# remo-v0_8_0-rc2-a.net
KiCad netlist of a schematic drawn in EasyEDA Pro
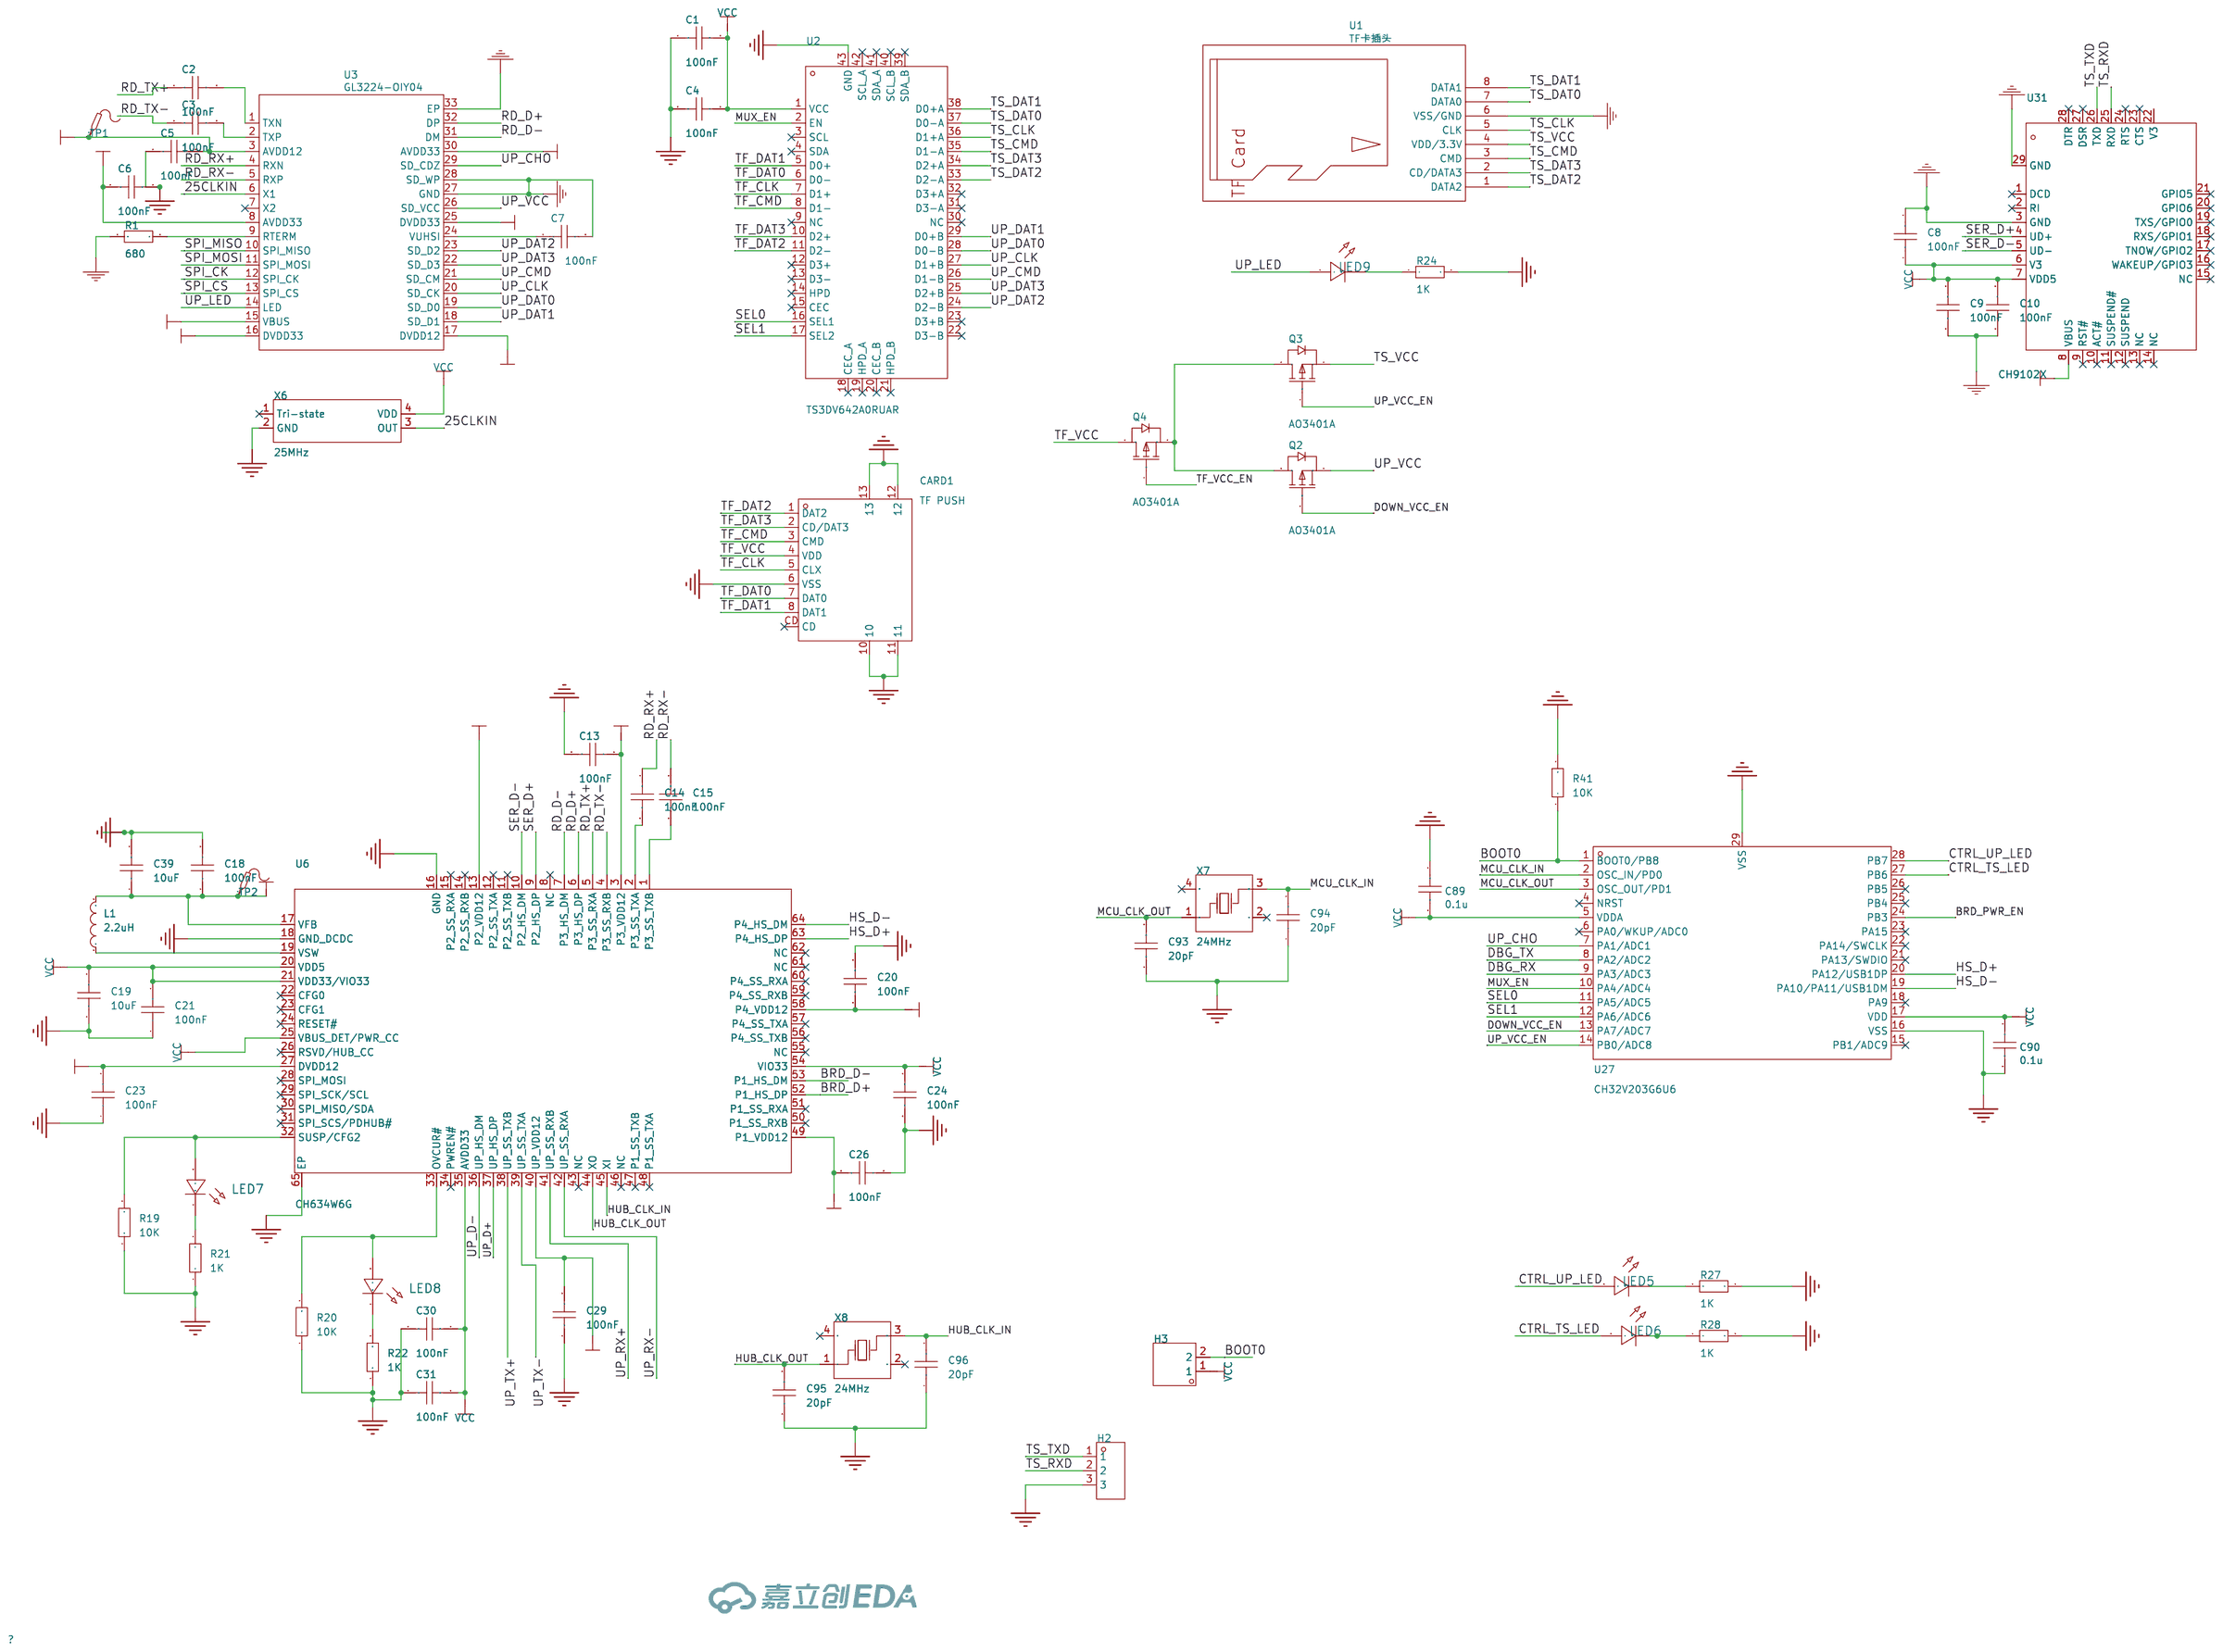
[diagram p0: main]
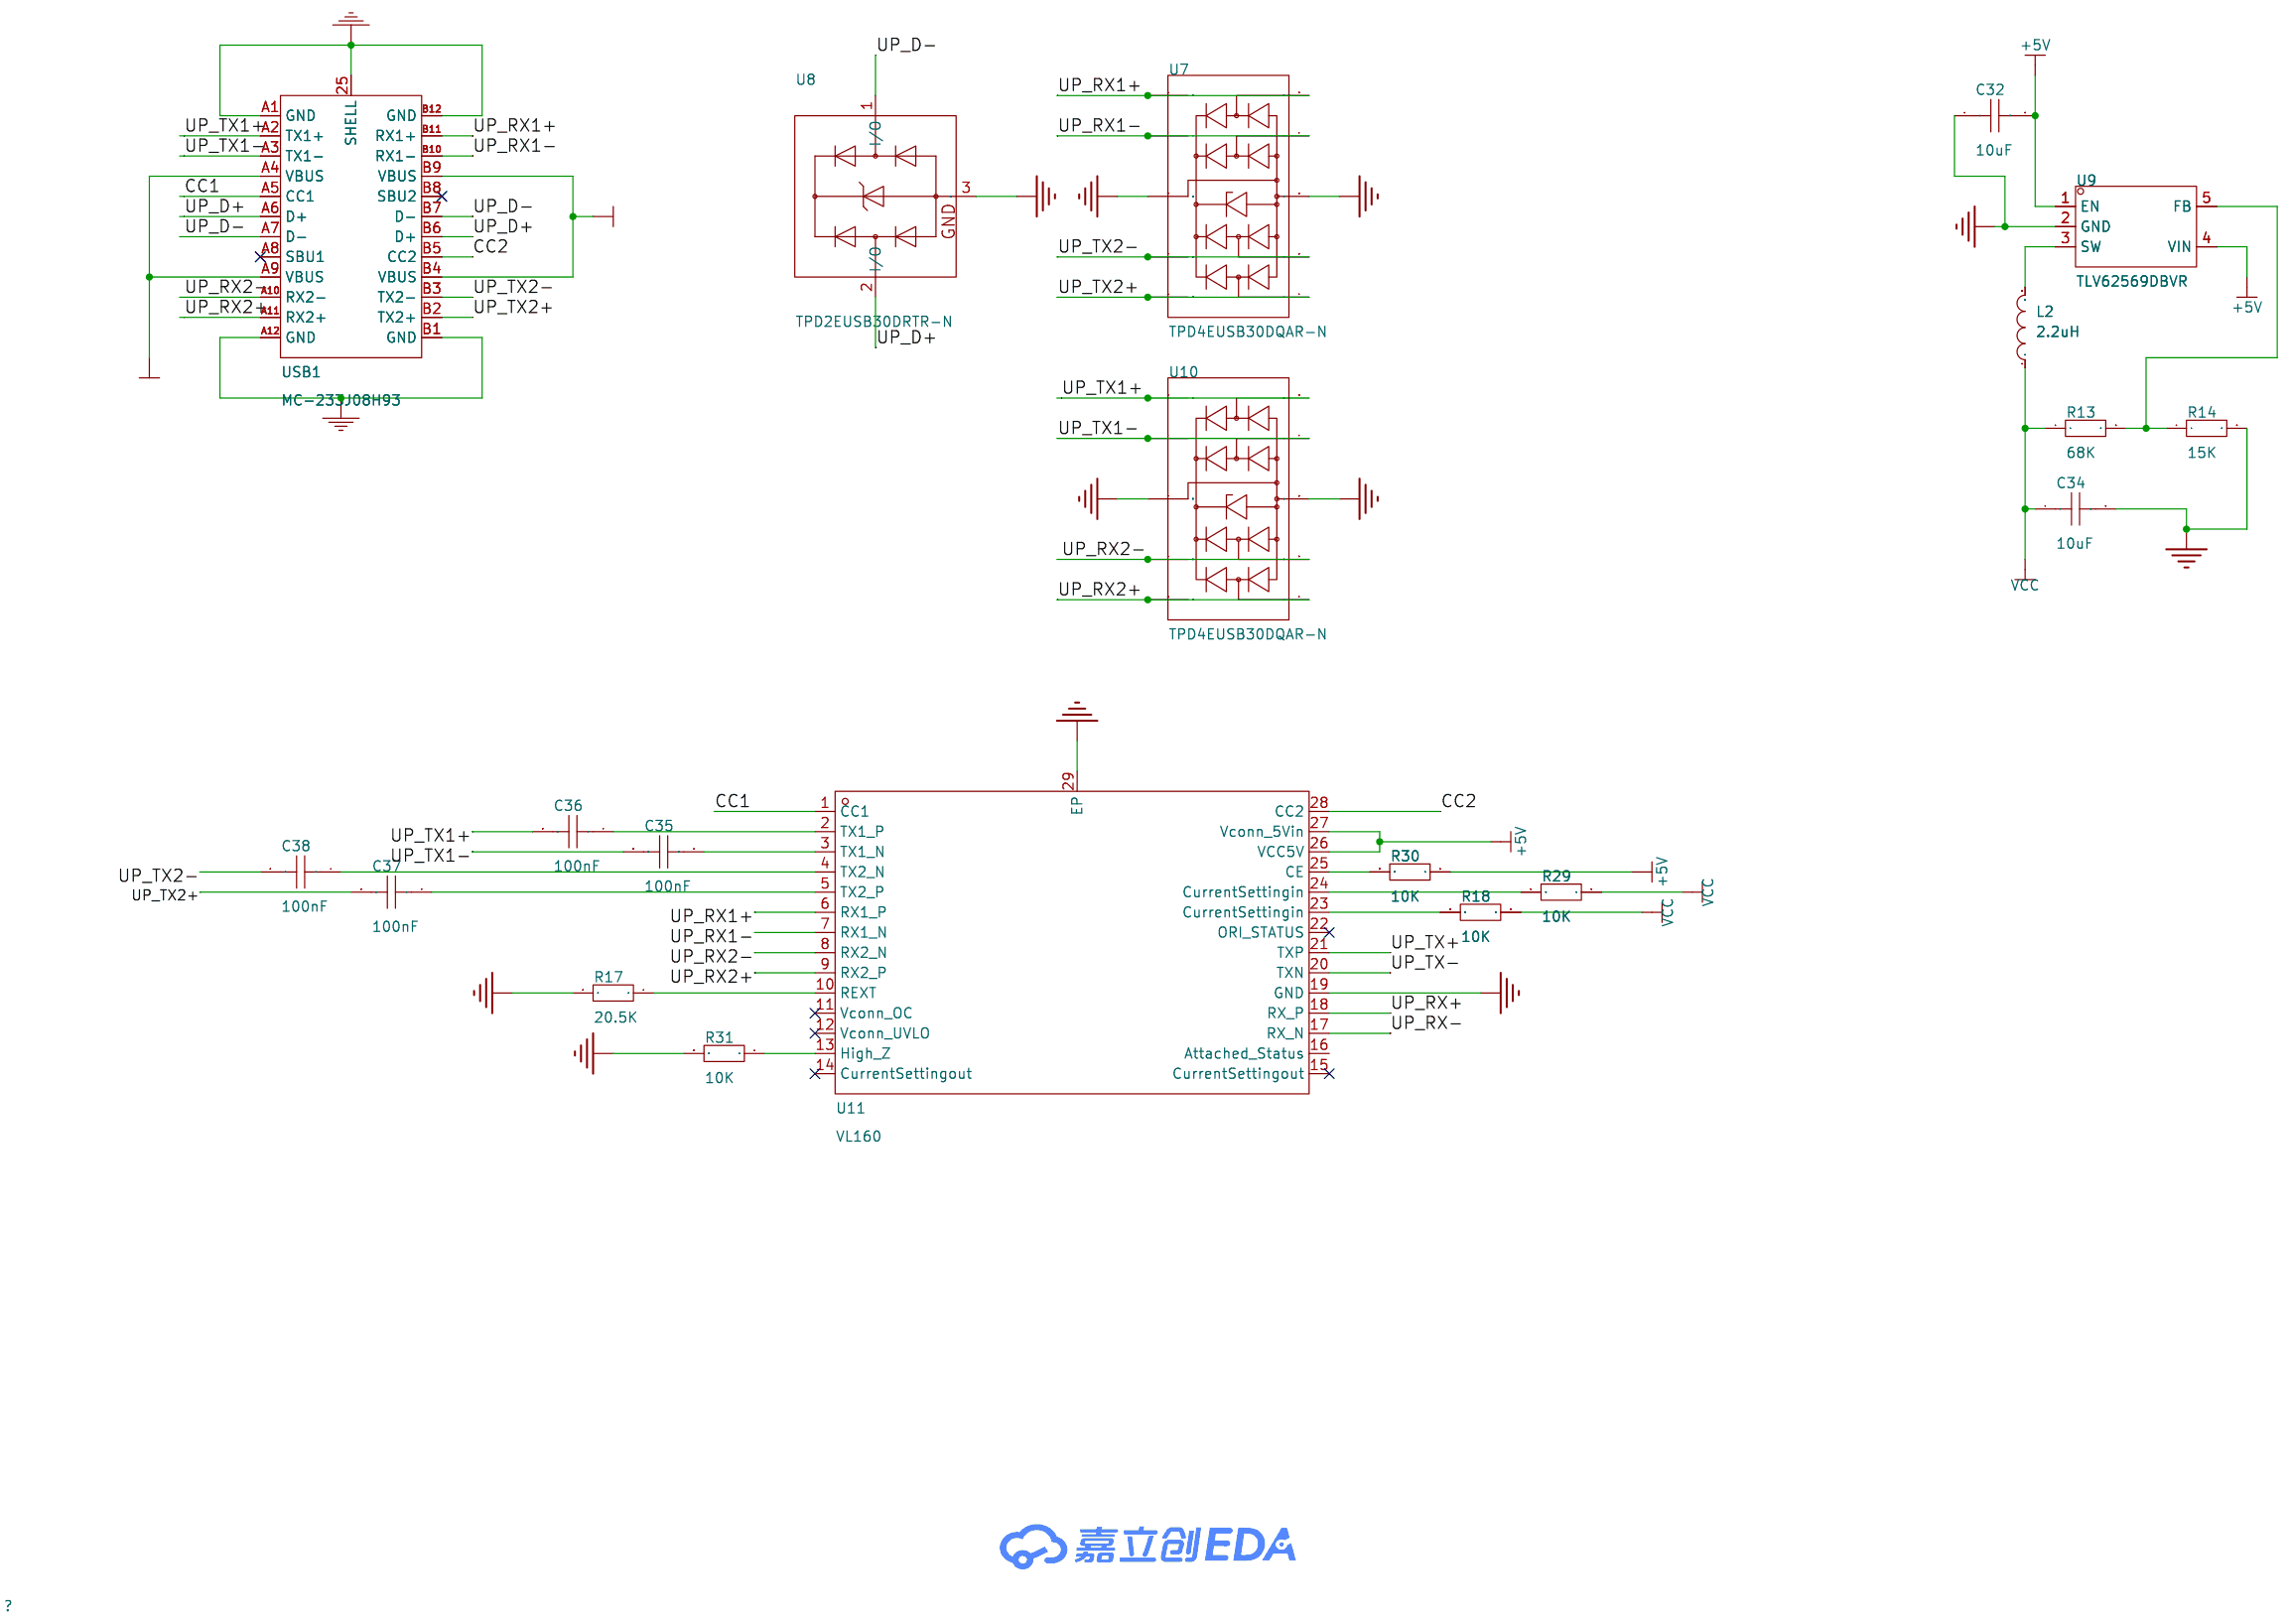
[diagram p1: typec_pwr]
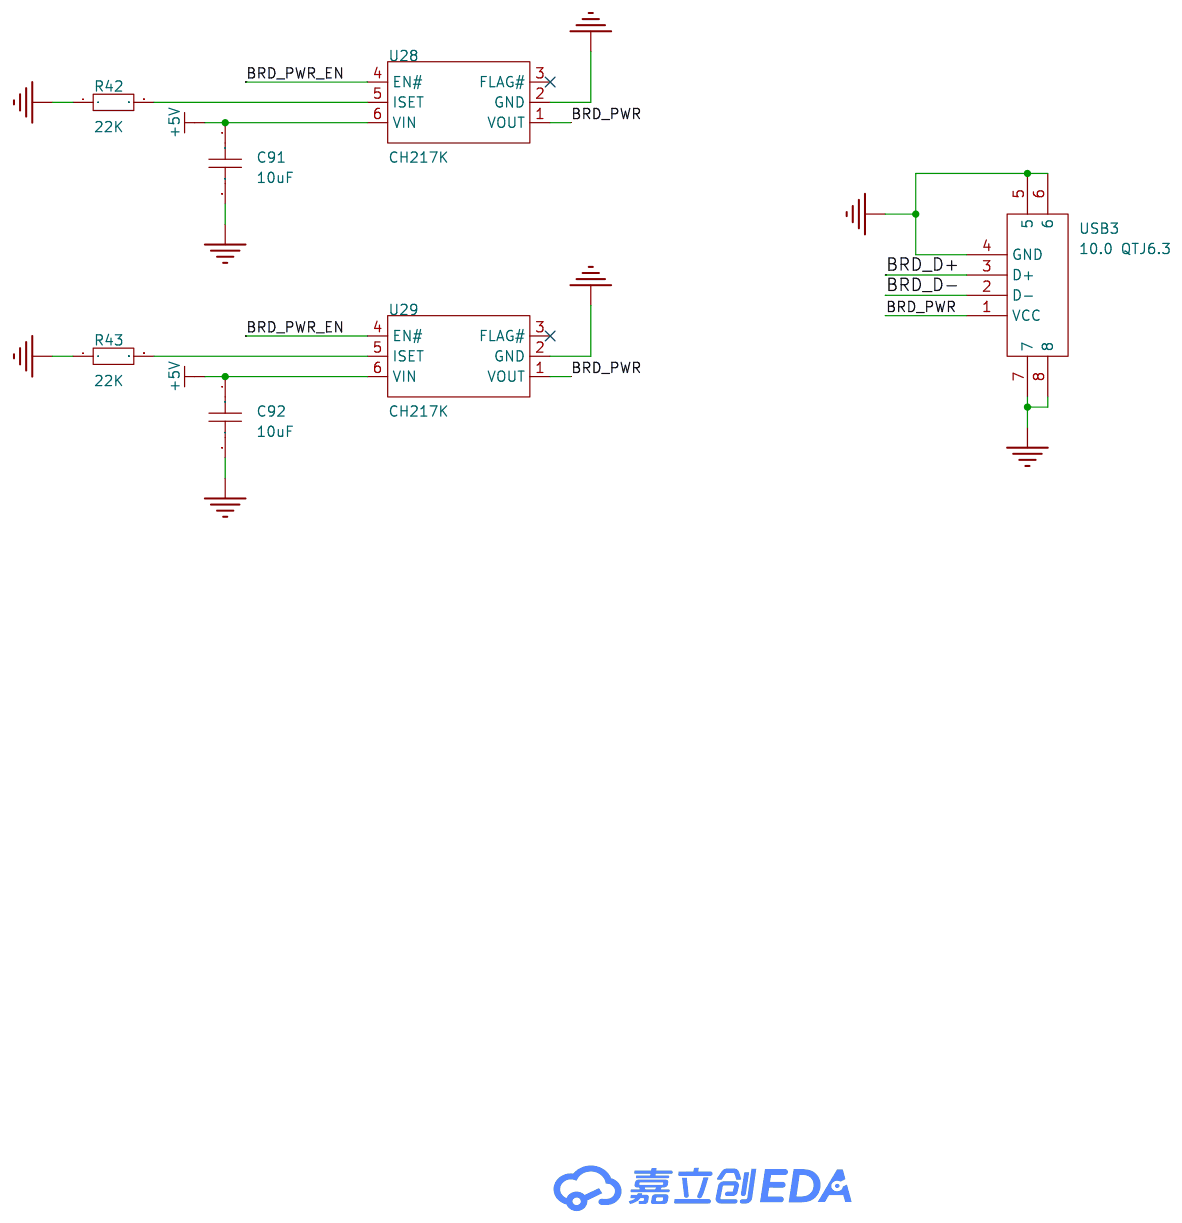
[diagram p2: power_ctrl]

(export (version "E")
  (design (tool "Eeschema 10.0.6"))
  (components
    (comp (ref "C1")
      (value "100nF")
      (footprint "easyedapro:C0402")
      (libsource (lib "easyedapro") (part "CapAcitance"))
    )
    (comp (ref "C2")
      (value "100nF")
      (footprint "easyedapro:C0402")
      (libsource (lib "easyedapro") (part "CapAcitance"))
    )
    (comp (ref "C3")
      (value "100nF")
      (footprint "easyedapro:C0402")
      (libsource (lib "easyedapro") (part "CapAcitance"))
    )
    (comp (ref "C4")
      (value "100nF")
      (footprint "easyedapro:C0402")
      (libsource (lib "easyedapro") (part "CapAcitance"))
    )
    (comp (ref "C5")
      (value "100nF")
      (footprint "easyedapro:C0402")
      (libsource (lib "easyedapro") (part "CapAcitance"))
    )
    (comp (ref "C6")
      (value "100nF")
      (footprint "easyedapro:C0402")
      (libsource (lib "easyedapro") (part "CapAcitance"))
    )
    (comp (ref "C7")
      (value "100nF")
      (footprint "easyedapro:C0402")
      (libsource (lib "easyedapro") (part "CapAcitance"))
    )
    (comp (ref "C8")
      (value "100nF")
      (footprint "easyedapro:C0402")
      (libsource (lib "easyedapro") (part "CapAcitance"))
    )
    (comp (ref "C9")
      (value "100nF")
      (footprint "easyedapro:C0402")
      (libsource (lib "easyedapro") (part "CapAcitance"))
    )
    (comp (ref "C10")
      (value "100nF")
      (footprint "easyedapro:C0402")
      (libsource (lib "easyedapro") (part "CapAcitance"))
    )
    (comp (ref "C13")
      (value "100nF")
      (footprint "easyedapro:C0402")
      (libsource (lib "easyedapro") (part "CapAcitance"))
    )
    (comp (ref "C14")
      (value "100nF")
      (footprint "easyedapro:C0402")
      (libsource (lib "easyedapro") (part "CapAcitance"))
    )
    (comp (ref "C15")
      (value "100nF")
      (footprint "easyedapro:C0402")
      (libsource (lib "easyedapro") (part "CapAcitance"))
    )
    (comp (ref "C18")
      (value "100nF")
      (footprint "easyedapro:C0402")
      (libsource (lib "easyedapro") (part "CapAcitance"))
    )
    (comp (ref "C19")
      (value "10uF")
      (footprint "easyedapro:C0402")
      (libsource (lib "easyedapro") (part "CapAcitance"))
    )
    (comp (ref "C20")
      (value "100nF")
      (footprint "easyedapro:C0402")
      (libsource (lib "easyedapro") (part "CapAcitance"))
    )
    (comp (ref "C21")
      (value "100nF")
      (footprint "easyedapro:C0402")
      (libsource (lib "easyedapro") (part "CapAcitance"))
    )
    (comp (ref "C23")
      (value "100nF")
      (footprint "easyedapro:C0402")
      (libsource (lib "easyedapro") (part "CapAcitance"))
    )
    (comp (ref "C24")
      (value "100nF")
      (footprint "easyedapro:C0402")
      (libsource (lib "easyedapro") (part "CapAcitance"))
    )
    (comp (ref "C26")
      (value "100nF")
      (footprint "easyedapro:C0402")
      (libsource (lib "easyedapro") (part "CapAcitance"))
    )
    (comp (ref "C29")
      (value "100nF")
      (footprint "easyedapro:C0402")
      (libsource (lib "easyedapro") (part "CapAcitance"))
    )
    (comp (ref "C30")
      (value "100nF")
      (footprint "easyedapro:C0402")
      (libsource (lib "easyedapro") (part "CapAcitance"))
    )
    (comp (ref "C31")
      (value "100nF")
      (footprint "easyedapro:C0402")
      (libsource (lib "easyedapro") (part "CapAcitance"))
    )
    (comp (ref "C39")
      (value "10uF")
      (footprint "easyedapro:C0402")
      (libsource (lib "easyedapro") (part "CapAcitance"))
    )
    (comp (ref "C89")
      (value "0.1u")
      (footprint "easyedapro:C0603")
      (libsource (lib "easyedapro") (part "0.1u"))
    )
    (comp (ref "C90")
      (value "0.1u")
      (footprint "easyedapro:C0603")
      (libsource (lib "easyedapro") (part "0.1u"))
    )
    (comp (ref "C93")
      (value "20pF")
      (footprint "easyedapro:C0402")
      (libsource (lib "easyedapro") (part "CapAcitance"))
    )
    (comp (ref "C94")
      (value "20pF")
      (footprint "easyedapro:C0402")
      (libsource (lib "easyedapro") (part "CapAcitance"))
    )
    (comp (ref "C95")
      (value "20pF")
      (footprint "easyedapro:C0402")
      (libsource (lib "easyedapro") (part "CapAcitance"))
    )
    (comp (ref "C96")
      (value "20pF")
      (footprint "easyedapro:C0402")
      (libsource (lib "easyedapro") (part "CapAcitance"))
    )
    (comp (ref "CARD1")
      (value "TF PUSH")
      (footprint "easyedapro:TF-SMD_TF-PUSH")
      (description "卡连接方式:自弹式;卡类型:MicroSD卡(TF卡);连接器类型:卡座;本体最大高度:2mm;工作温度范围:-20°C~+90°C;")
      (fields (field (name "Manufacturer") "SHOU HAN(首韩)"))
      (libsource (lib "easyedapro") (part "TF PUSH"))
    )
    (comp (ref "H2")
      (value "~")
      (footprint "easyedapro:HDR-TH_3P-P2.54-V-M")
      (libsource (lib "easyedapro") (part "PZ254V-11-03P_C2937625"))
    )
    (comp (ref "H3")
      (value "~")
      (footprint "easyedapro:HDR-TH_2P-P2.54-V-M-1")
      (libsource (lib "easyedapro") (part "210S-1*2P L=11.6MMGold-plated black"))
    )
    (comp (ref "L1")
      (value "2.2uH")
      (footprint "easyedapro:IND-SMD_L2.5-W2.0_MHCHL2520")
      (description "电感值:2.2uH;精度:±20%;额定电流:3A;饱和电流(Isat):3.8A;类型:一体成型电感;")
      (fields
        (field (name "Manufacturer Part") "FTC252012S2R2MBCA")
        (field (name "Manufacturer") "cjiang(长江微电)")
      )
      (libsource (lib "easyedapro") (part "FTC252012S2R2MBCA"))
    )
    (comp (ref "LED5")
      (value "~")
      (footprint "easyedapro:LED_0603")
      (libsource (lib "easyedapro") (part "LED_R"))
    )
    (comp (ref "LED6")
      (value "~")
      (footprint "easyedapro:LED_0603")
      (libsource (lib "easyedapro") (part "LED_R"))
    )
    (comp (ref "LED7")
      (value "~")
      (footprint "easyedapro:LED_0603")
      (libsource (lib "easyedapro") (part "LED_R"))
    )
    (comp (ref "LED8")
      (value "~")
      (footprint "easyedapro:LED_0603")
      (libsource (lib "easyedapro") (part "LED_R"))
    )
    (comp (ref "LED9")
      (value "~")
      (footprint "easyedapro:LED_0603")
      (libsource (lib "easyedapro") (part "LED_R"))
    )
    (comp (ref "Q2")
      (value "AO3401A")
      (footprint "easyedapro:SOT-23_L2.9-W1.3-P1.90-LS2.4-BR")
      (fields (field (name "Manufacturer") "AOS"))
      (libsource (lib "easyedapro") (part "AO3401A"))
    )
    (comp (ref "Q3")
      (value "AO3401A")
      (footprint "easyedapro:SOT-23_L2.9-W1.3-P1.90-LS2.4-BR")
      (fields (field (name "Manufacturer") "AOS"))
      (libsource (lib "easyedapro") (part "AO3401A"))
    )
    (comp (ref "Q4")
      (value "AO3401A")
      (footprint "easyedapro:SOT-23_L2.9-W1.3-P1.90-LS2.4-BR")
      (fields (field (name "Manufacturer") "AOS"))
      (libsource (lib "easyedapro") (part "AO3401A"))
    )
    (comp (ref "R1") (value "680") (footprint "easyedapro:R0603") (libsource (lib "easyedapro") (part "电阻")))
    (comp (ref "R19") (value "10K") (footprint "easyedapro:R0603") (libsource (lib "easyedapro") (part "电阻")))
    (comp (ref "R20") (value "10K") (footprint "easyedapro:R0603") (libsource (lib "easyedapro") (part "电阻")))
    (comp (ref "R21") (value "1K") (footprint "easyedapro:R0603") (libsource (lib "easyedapro") (part "电阻")))
    (comp (ref "R22") (value "1K") (footprint "easyedapro:R0603") (libsource (lib "easyedapro") (part "电阻")))
    (comp (ref "R24") (value "1K") (footprint "easyedapro:R0603") (libsource (lib "easyedapro") (part "电阻")))
    (comp (ref "R27") (value "1K") (footprint "easyedapro:R0603") (libsource (lib "easyedapro") (part "电阻")))
    (comp (ref "R28") (value "1K") (footprint "easyedapro:R0603") (libsource (lib "easyedapro") (part "电阻")))
    (comp (ref "R41") (value "10K") (footprint "easyedapro:R0603") (libsource (lib "easyedapro") (part "电阻")))
    (comp (ref "TP1")
      (value "~")
      (footprint "easyedapro:Test-Point-0.5mm")
      (description "Test Point 测试点")
      (libsource (lib "easyedapro") (part "Test-Point"))
    )
    (comp (ref "TP2")
      (value "~")
      (footprint "easyedapro:Test-Point-0.5mm")
      (description "Test Point 测试点")
      (libsource (lib "easyedapro") (part "Test-Point"))
    )
    (comp (ref "U1")
      (value "TF卡插头")
      (footprint "easyedapro:TF卡封装")
      (libsource (lib "easyedapro") (part "TF卡插头"))
    )
    (comp (ref "U2")
      (value "TS3DV642A0RUAR")
      (footprint "easyedapro:WFQFN-42_L9.0-W3.5-P0.50-BL-EP")
      (description "开关电路:单刀双掷(SPDT);通道数:12;导通电阻(Ron@VCC):9.5Ω;")
      (fields (field (name "Manufacturer") "TI(德州仪器)"))
      (libsource (lib "easyedapro") (part "TS3DV642A0RUAR"))
    )
    (comp (ref "U3")
      (value "GL3224-OIY04")
      (footprint "easyedapro:HQFN-32_L5.0-W5.0-P0.50-BL-EP3.0")
      (fields (field (name "Manufacturer") "GENESYS(创惟)"))
      (libsource (lib "easyedapro") (part "GL3224-OIY04"))
    )
    (comp (ref "U6")
      (value "CH634W6G")
      (footprint "easyedapro:QFN-64_L8.0-W8.0-P0.40-TL-EP6.2")
      (fields (field (name "Manufacturer") "WCH(南京沁恒)"))
      (libsource (lib "easyedapro") (part "CH634W6G"))
    )
    (comp (ref "U27")
      (value "CH32V203G6U6")
      (footprint "easyedapro:QFN-28_L4.0-W4.0-P0.40-BL-EP2.7")
      (description "CPU内核:RISC-V;GPIO端口数量:-;工作电压范围:-;CPU最大主频:-;程序存储器类型:-;应用领域:-;")
      (fields (field (name "Manufacturer") "WCH(南京沁恒)"))
      (libsource (lib "easyedapro") (part "CH32V203G6U6"))
    )
    (comp (ref "U31")
      (value "CH9102X")
      (footprint "easyedapro:TQFN-28_L5.0-W5.0-P0.50-BL-EP2.7")
      (description "应用功能:USB转UART;接口协议:USB 2.0;通道数:-;数据速率:4Mbps;")
      (fields (field (name "Manufacturer") "WCH(南京沁恒)"))
      (libsource (lib "easyedapro") (part "CH9102X_C5187522"))
    )
    (comp (ref "X6")
      (value "25MHz")
      (footprint "easyedapro:OSC-SMD_4P-L2.5-W2.0-BL-1")
      (description "频率:25MHz;常温频差:±10ppm;输出模式:CMOS;工作电压:1.8V~3.3V;频率稳定度:±20ppm;")
      (fields (field (name "Manufacturer Part") "OT252025MJBA4SL") (field (name "Manufacturer") "YXC(扬兴晶振)"))
      (libsource (lib "easyedapro") (part "OT252025MJBA4SL"))
    )
    (comp (ref "X7")
      (value "24MHz")
      (footprint "easyedapro:CRYSTAL-SMD_4P-L3.2-W2.5-BL")
      (description "晶振类型:贴片无源晶振;频率:24MHz;频率公差:±10ppm;频率稳定度:±30ppm;负载电容:20pF;工作温度:-40°C~+85°C;")
      (fields (field (name "Manufacturer Part") "X322524MSB4SI") (field (name "Manufacturer") "YXC(扬兴科技)"))
      (libsource (lib "easyedapro") (part "X322524MSB4SI"))
    )
    (comp (ref "X8")
      (value "24MHz")
      (footprint "easyedapro:CRYSTAL-SMD_4P-L3.2-W2.5-BL")
      (description "晶振类型:贴片无源晶振;频率:24MHz;频率公差:±10ppm;频率稳定度:±30ppm;负载电容:20pF;工作温度:-40°C~+85°C;")
      (fields (field (name "Manufacturer Part") "X322524MSB4SI") (field (name "Manufacturer") "YXC(扬兴科技)"))
      (libsource (lib "easyedapro") (part "X322524MSB4SI"))
    )
    (comp (ref "C32")
      (value "10uF")
      (footprint "easyedapro:C0402")
      (libsource (lib "easyedapro") (part "CapAcitance"))
    )
    (comp (ref "C34")
      (value "10uF")
      (footprint "easyedapro:C0402")
      (libsource (lib "easyedapro") (part "CapAcitance"))
    )
    (comp (ref "C35")
      (value "100nF")
      (footprint "easyedapro:C0402")
      (libsource (lib "easyedapro") (part "CapAcitance"))
    )
    (comp (ref "C36")
      (value "100nF")
      (footprint "easyedapro:C0402")
      (libsource (lib "easyedapro") (part "CapAcitance"))
    )
    (comp (ref "C37")
      (value "100nF")
      (footprint "easyedapro:C0402")
      (libsource (lib "easyedapro") (part "CapAcitance"))
    )
    (comp (ref "C38")
      (value "100nF")
      (footprint "easyedapro:C0402")
      (libsource (lib "easyedapro") (part "CapAcitance"))
    )
    (comp (ref "L2")
      (value "2.2uH")
      (footprint "easyedapro:IND-SMD_L2.5-W2.0_MHCHL2520")
      (description "电感值:2.2uH;精度:±20%;额定电流:3A;饱和电流(Isat):3.8A;类型:一体成型电感;")
      (fields
        (field (name "Manufacturer Part") "FTC252012S2R2MBCA")
        (field (name "Manufacturer") "cjiang(长江微电)")
      )
      (libsource (lib "easyedapro") (part "FTC252012S2R2MBCA"))
    )
    (comp (ref "R13") (value "68K") (footprint "easyedapro:R0603") (libsource (lib "easyedapro") (part "电阻")))
    (comp (ref "R14") (value "15K") (footprint "easyedapro:R0603") (libsource (lib "easyedapro") (part "电阻")))
    (comp (ref "R17")
      (value "20.5K")
      (footprint "easyedapro:R0603")
      (libsource (lib "easyedapro") (part "电阻"))
    )
    (comp (ref "R18") (value "10K") (footprint "easyedapro:R0603") (libsource (lib "easyedapro") (part "电阻")))
    (comp (ref "R29") (value "10K") (footprint "easyedapro:R0603") (libsource (lib "easyedapro") (part "电阻")))
    (comp (ref "R30") (value "10K") (footprint "easyedapro:R0603") (libsource (lib "easyedapro") (part "电阻")))
    (comp (ref "R31") (value "10K") (footprint "easyedapro:R0603") (libsource (lib "easyedapro") (part "电阻")))
    (comp (ref "U7")
      (value "TPD4EUSB30DQAR-N")
      (footprint "easyedapro:DFN-10_L2.5-W1.0-P0.50-BL-A")
      (description "极性:单向;反向截止电压(Vrwm):5V;")
      (fields (field (name "Manufacturer") "BORN(伯恩半导体)"))
      (libsource (lib "easyedapro") (part "TPD4EUSB30DQAR-N"))
    )
    (comp (ref "U8")
      (value "TPD2EUSB30DRTR-N")
      (footprint "easyedapro:SOT-723_L1.2-W0.8-P0.40-LS1.2-BR")
      (description "极性:单向;反向截止电压(Vrwm):5V;")
      (fields (field (name "Manufacturer") "BORN(伯恩半导体)"))
      (libsource (lib "easyedapro") (part "TPD2EUSB30DRTR-N"))
    )
    (comp (ref "U9")
      (value "TLV62569DBVR")
      (footprint "easyedapro:SOT-23-5_L3.0-W1.7-P0.95-LS2.8-BR")
      (description "功能类型:降压型;输出类型:可调;工作电压:2.5V~5.5V;输出电压:600mV~5.5V;输出电流:2A;")
      (fields (field (name "Manufacturer") "TI(德州仪器)"))
      (libsource (lib "easyedapro") (part "TLV62569DBVR"))
    )
    (comp (ref "U10")
      (value "TPD4EUSB30DQAR-N")
      (footprint "easyedapro:DFN-10_L2.5-W1.0-P0.50-BL-A")
      (description "极性:单向;反向截止电压(Vrwm):5V;")
      (fields (field (name "Manufacturer") "BORN(伯恩半导体)"))
      (libsource (lib "easyedapro") (part "TPD4EUSB30DQAR-N"))
    )
    (comp (ref "U11")
      (value "VL160")
      (footprint "easyedapro:MQFN-28_L4.5-W3.5-P0.40-BL-EP")
      (description "应用功能:-;接口协议:-;")
      (libsource (lib "easyedapro") (part "VL160"))
    )
    (comp (ref "USB1")
      (value "MC-233J08H93")
      (footprint "easyedapro:USB-C-SMD_TYPE-C-31-M-20")
      (fields (field (name "Manufacturer") "HANBO(汉博)"))
      (libsource (lib "easyedapro") (part "MC-233J08H93"))
    )
    (comp (ref "C91")
      (value "10uF")
      (footprint "easyedapro:C0402")
      (libsource (lib "easyedapro") (part "CapAcitance"))
    )
    (comp (ref "C92")
      (value "10uF")
      (footprint "easyedapro:C0402")
      (libsource (lib "easyedapro") (part "CapAcitance"))
    )
    (comp (ref "R42") (value "22K") (footprint "easyedapro:R0603") (libsource (lib "easyedapro") (part "电阻")))
    (comp (ref "R43") (value "22K") (footprint "easyedapro:R0603") (libsource (lib "easyedapro") (part "电阻")))
    (comp (ref "U28")
      (value "CH217K")
      (footprint "easyedapro:SOT-23-6_L2.9-W1.6-P0.95-LS2.8-BL")
      (description "类型:负载开关;通道数:1;输入控制逻辑:低电平有效;输出电流:2.7A;工作电压:2.7V~5.5V;导通电阻:70mΩ;")
      (fields (field (name "Manufacturer") "WCH(南京沁恒)"))
      (libsource (lib "easyedapro") (part "CH217K"))
    )
    (comp (ref "U29")
      (value "CH217K")
      (footprint "easyedapro:SOT-23-6_L2.9-W1.6-P0.95-LS2.8-BL")
      (description "类型:负载开关;通道数:1;输入控制逻辑:低电平有效;输出电流:2.7A;工作电压:2.7V~5.5V;导通电阻:70mΩ;")
      (fields (field (name "Manufacturer") "WCH(南京沁恒)"))
      (libsource (lib "easyedapro") (part "CH217K"))
    )
    (comp (ref "USB3")
      (value "10.0 QTJ6.3")
      (footprint "easyedapro:USB-A-SMD_10.0-QTJ6.3")
      (description "连接器类型:Type-A;标准:USB 2.0;公母:母;安装方式:卧贴;触点数量:4P;端口数量:1;额定电流 - 电源:1.5A;工作温度范围:-25°C~+85°C;")
      (fields (field (name "Manufacturer") "SHOU HAN(首韩)"))
      (libsource (lib "easyedapro") (part "10.0 QTJ6.3"))
    )
  )
  (nets
    (net (code "1") (name "+5V") (class "Default")
      (node (ref "C32") (pin "2") (pinfunction "2_2") (pintype "input"))
      (node (ref "C91") (pin "1") (pinfunction "1_1") (pintype "input"))
      (node (ref "C92") (pin "1") (pinfunction "1_1") (pintype "input"))
      (node (ref "R30") (pin "1") (pinfunction "1_1") (pintype "input"))
      (node (ref "U11") (pin "26") (pinfunction "VCC5V_26") (pintype "unspecified"))
      (node (ref "U11") (pin "27") (pinfunction "Vconn_5Vin_27") (pintype "unspecified"))
      (node (ref "U28") (pin "6") (pinfunction "VIN_6") (pintype "unspecified"))
      (node (ref "U29") (pin "6") (pinfunction "VIN_6") (pintype "unspecified"))
      (node (ref "U31") (pin "8") (pinfunction "VBUS_8") (pintype "unspecified"))
      (node (ref "U9") (pin "1") (pinfunction "EN_1") (pintype "unspecified"))
      (node (ref "U9") (pin "4") (pinfunction "VIN_4") (pintype "unspecified"))
      (node (ref "USB1") (pin "A4") (pinfunction "VBUS_A4") (pintype "unspecified"))
      (node (ref "USB1") (pin "A9") (pinfunction "VBUS_A9") (pintype "unspecified"))
      (node (ref "USB1") (pin "B4") (pinfunction "VBUS_B4") (pintype "unspecified"))
      (node (ref "USB1") (pin "B9") (pinfunction "VBUS_B9") (pintype "unspecified"))
    )
    (net (code "2") (name "25CLKIN") (class "Default")
      (node (ref "U3") (pin "6") (pinfunction "X1_6") (pintype "unspecified"))
      (node (ref "X6") (pin "3") (pinfunction "OUT_3") (pintype "unspecified"))
    )
    (net (code "3") (name "BOOT0") (class "Default")
      (node (ref "H3") (pin "2") (pinfunction "2_2") (pintype "unspecified"))
      (node (ref "R41") (pin "1") (pinfunction "1_1") (pintype "input"))
      (node (ref "U27") (pin "1") (pinfunction "BOOT0/PB8_1") (pintype "unspecified"))
    )
    (net (code "4") (name "BRD_D+") (class "Default")
      (node (ref "U6") (pin "52") (pinfunction "P1_HS_DP_52") (pintype "unspecified"))
      (node (ref "USB3") (pin "3") (pinfunction "D+_3") (pintype "unspecified"))
    )
    (net (code "5") (name "BRD_D-") (class "Default")
      (node (ref "U6") (pin "53") (pinfunction "P1_HS_DM_53") (pintype "unspecified"))
      (node (ref "USB3") (pin "2") (pinfunction "D-_2") (pintype "unspecified"))
    )
    (net (code "6") (name "BRD_PWR") (class "Default")
      (node (ref "U28") (pin "1") (pinfunction "VOUT_1") (pintype "unspecified"))
      (node (ref "U29") (pin "1") (pinfunction "VOUT_1") (pintype "unspecified"))
      (node (ref "USB3") (pin "1") (pinfunction "VCC_1") (pintype "unspecified"))
    )
    (net (code "7") (name "BRD_PWR_EN") (class "Default")
      (node (ref "U27") (pin "24") (pinfunction "PB3_24") (pintype "unspecified"))
      (node (ref "U28") (pin "4") (pinfunction "EN#_4") (pintype "unspecified"))
      (node (ref "U29") (pin "4") (pinfunction "EN#_4") (pintype "unspecified"))
    )
    (net (code "8") (name "CC1") (class "Default")
      (node (ref "U11") (pin "1") (pinfunction "CC1_1") (pintype "unspecified"))
      (node (ref "USB1") (pin "A5") (pinfunction "CC1_A5") (pintype "unspecified"))
    )
    (net (code "9") (name "CC2") (class "Default")
      (node (ref "U11") (pin "28") (pinfunction "CC2_28") (pintype "unspecified"))
      (node (ref "USB1") (pin "B5") (pinfunction "CC2_B5") (pintype "unspecified"))
    )
    (net (code "10") (name "CTRL_TS_LED") (class "Default")
      (node (ref "LED6") (pin "2") (pinfunction "A_2") (pintype "input"))
      (node (ref "U27") (pin "27") (pinfunction "PB6_27") (pintype "unspecified"))
    )
    (net (code "11") (name "CTRL_UP_LED") (class "Default")
      (node (ref "LED5") (pin "2") (pinfunction "A_2") (pintype "input"))
      (node (ref "U27") (pin "28") (pinfunction "PB7_28") (pintype "unspecified"))
    )
    (net (code "12") (name "DBG_RX") (class "Default")
      (node (ref "U27") (pin "9") (pinfunction "PA3/ADC3_9") (pintype "unspecified"))
    )
    (net (code "13") (name "DBG_TX") (class "Default")
      (node (ref "U27") (pin "8") (pinfunction "PA2/ADC2_8") (pintype "unspecified"))
    )
    (net (code "14") (name "DOWN_VCC_EN") (class "Default")
      (node (ref "Q2") (pin "1") (pinfunction "G_1") (pintype "unspecified"))
      (node (ref "U27") (pin "13") (pinfunction "PA7/ADC7_13") (pintype "unspecified"))
    )
    (net (code "15") (name "GND") (class "Default")
      (node (ref "C1") (pin "1") (pinfunction "1_1") (pintype "input"))
      (node (ref "C10") (pin "1") (pinfunction "1_1") (pintype "input"))
      (node (ref "C13") (pin "2") (pinfunction "2_2") (pintype "input"))
      (node (ref "C18") (pin "2") (pinfunction "2_2") (pintype "input"))
      (node (ref "C19") (pin "1") (pinfunction "1_1") (pintype "input"))
      (node (ref "C20") (pin "2") (pinfunction "2_2") (pintype "input"))
      (node (ref "C21") (pin "1") (pinfunction "1_1") (pintype "input"))
      (node (ref "C23") (pin "1") (pinfunction "1_1") (pintype "input"))
      (node (ref "C24") (pin "2") (pinfunction "2_2") (pintype "input"))
      (node (ref "C26") (pin "1") (pinfunction "1_1") (pintype "input"))
      (node (ref "C29") (pin "1") (pinfunction "1_1") (pintype "input"))
      (node (ref "C30") (pin "1") (pinfunction "1_1") (pintype "input"))
      (node (ref "C31") (pin "1") (pinfunction "1_1") (pintype "input"))
      (node (ref "C32") (pin "1") (pinfunction "1_1") (pintype "input"))
      (node (ref "C34") (pin "2") (pinfunction "2_2") (pintype "input"))
      (node (ref "C39") (pin "2") (pinfunction "2_2") (pintype "input"))
      (node (ref "C4") (pin "1") (pinfunction "1_1") (pintype "input"))
      (node (ref "C5") (pin "1") (pinfunction "1_1") (pintype "input"))
      (node (ref "C6") (pin "2") (pinfunction "2_2") (pintype "input"))
      (node (ref "C7") (pin "2") (pinfunction "2_2") (pintype "input"))
      (node (ref "C8") (pin "2") (pinfunction "2_2") (pintype "input"))
      (node (ref "C89") (pin "1") (pinfunction "1_1") (pintype "unspecified"))
      (node (ref "C9") (pin "1") (pinfunction "1_1") (pintype "input"))
      (node (ref "C90") (pin "2") (pinfunction "2_2") (pintype "unspecified"))
      (node (ref "C91") (pin "2") (pinfunction "2_2") (pintype "input"))
      (node (ref "C92") (pin "2") (pinfunction "2_2") (pintype "input"))
      (node (ref "C93") (pin "1") (pinfunction "1_1") (pintype "input"))
      (node (ref "C94") (pin "1") (pinfunction "1_1") (pintype "input"))
      (node (ref "C95") (pin "1") (pinfunction "1_1") (pintype "input"))
      (node (ref "C96") (pin "1") (pinfunction "1_1") (pintype "input"))
      (node (ref "CARD1") (pin "10") (pinfunction "10_10") (pintype "unspecified"))
      (node (ref "CARD1") (pin "11") (pinfunction "11_11") (pintype "unspecified"))
      (node (ref "CARD1") (pin "12") (pinfunction "12_12") (pintype "unspecified"))
      (node (ref "CARD1") (pin "13") (pinfunction "13_13") (pintype "unspecified"))
      (node (ref "CARD1") (pin "6") (pinfunction "VSS_6") (pintype "unspecified"))
      (node (ref "H2") (pin "3") (pinfunction "3_3") (pintype "input"))
      (node (ref "R1") (pin "1") (pinfunction "1_1") (pintype "input"))
      (node (ref "R14") (pin "2") (pinfunction "2_2") (pintype "input"))
      (node (ref "R17") (pin "2") (pinfunction "2_2") (pintype "input"))
      (node (ref "R19") (pin "1") (pinfunction "1_1") (pintype "input"))
      (node (ref "R20") (pin "1") (pinfunction "1_1") (pintype "input"))
      (node (ref "R21") (pin "1") (pinfunction "1_1") (pintype "input"))
      (node (ref "R22") (pin "1") (pinfunction "1_1") (pintype "input"))
      (node (ref "R24") (pin "2") (pinfunction "2_2") (pintype "input"))
      (node (ref "R27") (pin "2") (pinfunction "2_2") (pintype "input"))
      (node (ref "R28") (pin "2") (pinfunction "2_2") (pintype "input"))
      (node (ref "R31") (pin "2") (pinfunction "2_2") (pintype "input"))
      (node (ref "R41") (pin "2") (pinfunction "2_2") (pintype "input"))
      (node (ref "R42") (pin "1") (pinfunction "1_1") (pintype "input"))
      (node (ref "R43") (pin "1") (pinfunction "1_1") (pintype "input"))
      (node (ref "U1") (pin "6") (pinfunction "VSS/GND_6") (pintype "unspecified"))
      (node (ref "U10") (pin "3") (pinfunction "3_3") (pintype "unspecified"))
      (node (ref "U10") (pin "8") (pinfunction "8_8") (pintype "unspecified"))
      (node (ref "U11") (pin "19") (pinfunction "GND_19") (pintype "unspecified"))
      (node (ref "U11") (pin "29") (pinfunction "EP_29") (pintype "unspecified"))
      (node (ref "U2") (pin "43") (pinfunction "GND_43") (pintype "unspecified"))
      (node (ref "U27") (pin "16") (pinfunction "VSS_16") (pintype "unspecified"))
      (node (ref "U27") (pin "29") (pinfunction "VSS_29") (pintype "unspecified"))
      (node (ref "U28") (pin "2") (pinfunction "GND_2") (pintype "unspecified"))
      (node (ref "U29") (pin "2") (pinfunction "GND_2") (pintype "unspecified"))
      (node (ref "U3") (pin "27") (pinfunction "GND_27") (pintype "unspecified"))
      (node (ref "U3") (pin "28") (pinfunction "SD_WP_28") (pintype "unspecified"))
      (node (ref "U3") (pin "33") (pinfunction "EP_33") (pintype "unspecified"))
      (node (ref "U31") (pin "29") (pinfunction "GND_29") (pintype "unspecified"))
      (node (ref "U31") (pin "3") (pinfunction "GND_3") (pintype "unspecified"))
      (node (ref "U6") (pin "16") (pinfunction "GND_16") (pintype "unspecified"))
      (node (ref "U6") (pin "18") (pinfunction "GND_DCDC_18") (pintype "unspecified"))
      (node (ref "U6") (pin "65") (pinfunction "EP_65") (pintype "unspecified"))
      (node (ref "U7") (pin "3") (pinfunction "3_3") (pintype "unspecified"))
      (node (ref "U7") (pin "8") (pinfunction "8_8") (pintype "unspecified"))
      (node (ref "U8") (pin "3") (pinfunction "GND_3") (pintype "unspecified"))
      (node (ref "U9") (pin "2") (pinfunction "GND_2") (pintype "unspecified"))
      (node (ref "USB1") (pin "25") (pinfunction "SHELL_25") (pintype "unspecified"))
      (node (ref "USB1") (pin "A1") (pinfunction "GND_A1") (pintype "unspecified"))
      (node (ref "USB1") (pin "A12") (pinfunction "GND_A12") (pintype "unspecified"))
      (node (ref "USB1") (pin "B1") (pinfunction "GND_B1") (pintype "unspecified"))
      (node (ref "USB1") (pin "B12") (pinfunction "GND_B12") (pintype "unspecified"))
      (node (ref "USB3") (pin "4") (pinfunction "GND_4") (pintype "unspecified"))
      (node (ref "USB3") (pin "5") (pinfunction "5_5") (pintype "unspecified"))
      (node (ref "USB3") (pin "6") (pinfunction "6_6") (pintype "unspecified"))
      (node (ref "USB3") (pin "7") (pinfunction "7_7") (pintype "unspecified"))
      (node (ref "USB3") (pin "8") (pinfunction "8_8") (pintype "unspecified"))
      (node (ref "X6") (pin "2") (pinfunction "GND_2") (pintype "unspecified"))
    )
    (net (code "16") (name "HS_D+") (class "Default")
      (node (ref "U27") (pin "20") (pinfunction "PA12/USB1DP_20") (pintype "unspecified"))
      (node (ref "U6") (pin "63") (pinfunction "P4_HS_DP_63") (pintype "unspecified"))
    )
    (net (code "17") (name "HS_D-") (class "Default")
      (node (ref "U27") (pin "19") (pinfunction "PA10/PA11/USB1DM_19") (pintype "unspecified"))
      (node (ref "U6") (pin "64") (pinfunction "P4_HS_DM_64") (pintype "unspecified"))
    )
    (net (code "18") (name "HUB_CLK_IN") (class "Default")
      (node (ref "C96") (pin "2") (pinfunction "2_2") (pintype "input"))
      (node (ref "U6") (pin "45") (pinfunction "XI_45") (pintype "unspecified"))
      (node (ref "X8") (pin "3") (pinfunction "OSC2_3") (pintype "input"))
    )
    (net (code "19") (name "HUB_CLK_OUT") (class "Default")
      (node (ref "C95") (pin "2") (pinfunction "2_2") (pintype "input"))
      (node (ref "U6") (pin "44") (pinfunction "XO_44") (pintype "unspecified"))
      (node (ref "X8") (pin "1") (pinfunction "OSC1_1") (pintype "input"))
    )
    (net (code "20") (name "MCU_CLK_IN") (class "Default")
      (node (ref "C94") (pin "2") (pinfunction "2_2") (pintype "input"))
      (node (ref "U27") (pin "2") (pinfunction "OSC_IN/PD0_2") (pintype "unspecified"))
      (node (ref "X7") (pin "3") (pinfunction "OSC2_3") (pintype "input"))
    )
    (net (code "21") (name "MCU_CLK_OUT") (class "Default")
      (node (ref "C93") (pin "2") (pinfunction "2_2") (pintype "input"))
      (node (ref "U27") (pin "3") (pinfunction "OSC_OUT/PD1_3") (pintype "unspecified"))
      (node (ref "X7") (pin "1") (pinfunction "OSC1_1") (pintype "input"))
    )
    (net (code "22") (name "MUX_EN") (class "Default")
      (node (ref "U2") (pin "2") (pinfunction "EN_2") (pintype "unspecified"))
      (node (ref "U27") (pin "10") (pinfunction "PA4/ADC4_10") (pintype "unspecified"))
    )
    (net (code "23") (name "Net-(LED5-C)") (class "Default")
      (node (ref "LED5") (pin "1") (pinfunction "C_1") (pintype "input"))
      (node (ref "R27") (pin "1") (pinfunction "1_1") (pintype "input"))
    )
    (net (code "24") (name "Net-(LED6-C)") (class "Default")
      (node (ref "LED6") (pin "1") (pinfunction "C_1") (pintype "input"))
      (node (ref "R28") (pin "1") (pinfunction "1_1") (pintype "input"))
    )
    (net (code "25") (name "Net-(LED7-A)") (class "Default")
      (node (ref "LED7") (pin "2") (pinfunction "A_2") (pintype "input"))
      (node (ref "R19") (pin "2") (pinfunction "2_2") (pintype "input"))
      (node (ref "U6") (pin "32") (pinfunction "SUSP/CFG2_32") (pintype "unspecified"))
    )
    (net (code "26") (name "Net-(LED7-C)") (class "Default")
      (node (ref "LED7") (pin "1") (pinfunction "C_1") (pintype "input"))
      (node (ref "R21") (pin "2") (pinfunction "2_2") (pintype "input"))
    )
    (net (code "27") (name "Net-(LED8-A)") (class "Default")
      (node (ref "LED8") (pin "2") (pinfunction "A_2") (pintype "input"))
      (node (ref "R20") (pin "2") (pinfunction "2_2") (pintype "input"))
      (node (ref "U6") (pin "33") (pinfunction "OVCUR#_33") (pintype "unspecified"))
    )
    (net (code "28") (name "Net-(LED8-C)") (class "Default")
      (node (ref "LED8") (pin "1") (pinfunction "C_1") (pintype "input"))
      (node (ref "R22") (pin "2") (pinfunction "2_2") (pintype "input"))
    )
    (net (code "29") (name "Net-(LED9-C)") (class "Default")
      (node (ref "LED9") (pin "1") (pinfunction "C_1") (pintype "input"))
      (node (ref "R24") (pin "1") (pinfunction "1_1") (pintype "input"))
    )
    (net (code "30") (name "Net-(Q2-D)") (class "Default")
      (node (ref "Q2") (pin "3") (pinfunction "D_3") (pintype "unspecified"))
      (node (ref "Q3") (pin "3") (pinfunction "D_3") (pintype "unspecified"))
      (node (ref "Q4") (pin "2") (pinfunction "S_2") (pintype "unspecified"))
    )
    (net (code "31") (name "Net-(R18-Pad2)") (class "Default")
      (node (ref "R18") (pin "2") (pinfunction "2_2") (pintype "input"))
      (node (ref "U11") (pin "23") (pinfunction "CurrentSettingin_23") (pintype "unspecified"))
    )
    (net (code "32") (name "Net-(R29-Pad2)") (class "Default")
      (node (ref "R29") (pin "2") (pinfunction "2_2") (pintype "input"))
      (node (ref "U11") (pin "24") (pinfunction "CurrentSettingin_24") (pintype "unspecified"))
    )
    (net (code "33") (name "Net-(U3-RTERM)") (class "Default")
      (node (ref "R1") (pin "2") (pinfunction "2_2") (pintype "input"))
      (node (ref "U3") (pin "9") (pinfunction "RTERM_9") (pintype "unspecified"))
    )
    (net (code "34") (name "Net-(U3-TXN)") (class "Default")
      (node (ref "C2") (pin "2") (pinfunction "2_2") (pintype "input"))
      (node (ref "U3") (pin "1") (pinfunction "TXN_1") (pintype "unspecified"))
    )
    (net (code "35") (name "Net-(U3-TXP)") (class "Default")
      (node (ref "C3") (pin "2") (pinfunction "2_2") (pintype "input"))
      (node (ref "U3") (pin "2") (pinfunction "TXP_2") (pintype "unspecified"))
    )
    (net (code "36") (name "Net-(U3-VUHSI)") (class "Default")
      (node (ref "C7") (pin "1") (pinfunction "1_1") (pintype "input"))
      (node (ref "U3") (pin "24") (pinfunction "VUHSI_24") (pintype "unspecified"))
    )
    (net (code "37") (name "Net-(U6-P3_SS_TXA)") (class "Default")
      (node (ref "C14") (pin "2") (pinfunction "2_2") (pintype "input"))
      (node (ref "U6") (pin "2") (pinfunction "P3_SS_TXA_2") (pintype "unspecified"))
    )
    (net (code "38") (name "Net-(U6-P3_SS_TXB)") (class "Default")
      (node (ref "C15") (pin "2") (pinfunction "2_2") (pintype "input"))
      (node (ref "U6") (pin "1") (pinfunction "P3_SS_TXB_1") (pintype "unspecified"))
    )
    (net (code "39") (name "Net-(U6-VSW)") (class "Default")
      (node (ref "L1") (pin "1") (pinfunction "1_1") (pintype "unspecified"))
      (node (ref "U6") (pin "19") (pinfunction "VSW_19") (pintype "unspecified"))
    )
    (net (code "40") (name "Net-(U9-FB)") (class "Default")
      (node (ref "R13") (pin "2") (pinfunction "2_2") (pintype "input"))
      (node (ref "R14") (pin "1") (pinfunction "1_1") (pintype "input"))
      (node (ref "U9") (pin "5") (pinfunction "FB_5") (pintype "unspecified"))
    )
    (net (code "41") (name "Net-(U9-SW)") (class "Default")
      (node (ref "L2") (pin "2") (pinfunction "2_2") (pintype "unspecified"))
      (node (ref "U9") (pin "3") (pinfunction "SW_3") (pintype "unspecified"))
    )
    (net (code "42") (name "Net-(U11-CE)") (class "Default")
      (node (ref "R30") (pin "2") (pinfunction "2_2") (pintype "input"))
      (node (ref "U11") (pin "25") (pinfunction "CE_25") (pintype "unspecified"))
    )
    (net (code "43") (name "Net-(U11-High_Z)") (class "Default")
      (node (ref "R31") (pin "1") (pinfunction "1_1") (pintype "input"))
      (node (ref "U11") (pin "13") (pinfunction "High_Z_13") (pintype "unspecified"))
    )
    (net (code "44") (name "Net-(U11-REXT)") (class "Default")
      (node (ref "R17") (pin "1") (pinfunction "1_1") (pintype "input"))
      (node (ref "U11") (pin "10") (pinfunction "REXT_10") (pintype "unspecified"))
    )
    (net (code "45") (name "Net-(U11-TX1_N)") (class "Default")
      (node (ref "C35") (pin "1") (pinfunction "1_1") (pintype "input"))
      (node (ref "U11") (pin "3") (pinfunction "TX1_N_3") (pintype "unspecified"))
    )
    (net (code "46") (name "Net-(U11-TX1_P)") (class "Default")
      (node (ref "C36") (pin "1") (pinfunction "1_1") (pintype "input"))
      (node (ref "U11") (pin "2") (pinfunction "TX1_P_2") (pintype "unspecified"))
    )
    (net (code "47") (name "Net-(U11-TX2_N)") (class "Default")
      (node (ref "C38") (pin "1") (pinfunction "1_1") (pintype "input"))
      (node (ref "U11") (pin "4") (pinfunction "TX2_N_4") (pintype "unspecified"))
    )
    (net (code "48") (name "Net-(U11-TX2_P)") (class "Default")
      (node (ref "C37") (pin "1") (pinfunction "1_1") (pintype "input"))
      (node (ref "U11") (pin "5") (pinfunction "TX2_P_5") (pintype "unspecified"))
    )
    (net (code "49") (name "Net-(U28-ISET)") (class "Default")
      (node (ref "R42") (pin "2") (pinfunction "2_2") (pintype "input"))
      (node (ref "U28") (pin "5") (pinfunction "ISET_5") (pintype "unspecified"))
    )
    (net (code "50") (name "Net-(U29-ISET)") (class "Default")
      (node (ref "R43") (pin "2") (pinfunction "2_2") (pintype "input"))
      (node (ref "U29") (pin "5") (pinfunction "ISET_5") (pintype "unspecified"))
    )
    (net (code "51") (name "RD_1V2") (class "Default")
      (node (ref "C5") (pin "2") (pinfunction "2_2") (pintype "input"))
      (node (ref "TP1") (pin "1") (pinfunction "1_1") (pintype "input"))
      (node (ref "U3") (pin "17") (pinfunction "DVDD12_17") (pintype "unspecified"))
      (node (ref "U3") (pin "3") (pinfunction "AVDD12_3") (pintype "unspecified"))
    )
    (net (code "52") (name "RD_D+") (class "Default")
      (node (ref "U3") (pin "32") (pinfunction "DP_32") (pintype "unspecified"))
      (node (ref "U6") (pin "6") (pinfunction "P3_HS_DP_6") (pintype "unspecified"))
    )
    (net (code "53") (name "RD_D-") (class "Default")
      (node (ref "U3") (pin "31") (pinfunction "DM_31") (pintype "unspecified"))
      (node (ref "U6") (pin "7") (pinfunction "P3_HS_DM_7") (pintype "unspecified"))
    )
    (net (code "54") (name "RD_RX+") (class "Default")
      (node (ref "C14") (pin "1") (pinfunction "1_1") (pintype "input"))
      (node (ref "U3") (pin "4") (pinfunction "RXN_4") (pintype "unspecified"))
    )
    (net (code "55") (name "RD_RX-") (class "Default")
      (node (ref "C15") (pin "1") (pinfunction "1_1") (pintype "input"))
      (node (ref "U3") (pin "5") (pinfunction "RXP_5") (pintype "unspecified"))
    )
    (net (code "56") (name "RD_TX+") (class "Default")
      (node (ref "C2") (pin "1") (pinfunction "1_1") (pintype "input"))
      (node (ref "U6") (pin "5") (pinfunction "P3_SS_RXA_5") (pintype "unspecified"))
    )
    (net (code "57") (name "RD_TX-") (class "Default")
      (node (ref "C3") (pin "1") (pinfunction "1_1") (pintype "input"))
      (node (ref "U6") (pin "4") (pinfunction "P3_SS_RXB_4") (pintype "unspecified"))
    )
    (net (code "58") (name "SEL0") (class "Default")
      (node (ref "U2") (pin "16") (pinfunction "SEL1_16") (pintype "unspecified"))
      (node (ref "U27") (pin "11") (pinfunction "PA5/ADC5_11") (pintype "unspecified"))
    )
    (net (code "59") (name "SEL1") (class "Default")
      (node (ref "U2") (pin "17") (pinfunction "SEL2_17") (pintype "unspecified"))
      (node (ref "U27") (pin "12") (pinfunction "PA6/ADC6_12") (pintype "unspecified"))
    )
    (net (code "60") (name "SER_D+") (class "Default")
      (node (ref "U31") (pin "4") (pinfunction "UD+_4") (pintype "unspecified"))
      (node (ref "U6") (pin "9") (pinfunction "P2_HS_DP_9") (pintype "unspecified"))
    )
    (net (code "61") (name "SER_D-") (class "Default")
      (node (ref "U31") (pin "5") (pinfunction "UD-_5") (pintype "unspecified"))
      (node (ref "U6") (pin "10") (pinfunction "P2_HS_DM_10") (pintype "unspecified"))
    )
    (net (code "62") (name "SPI_CK") (class "Default")
      (node (ref "U3") (pin "12") (pinfunction "SPI_CK_12") (pintype "unspecified"))
    )
    (net (code "63") (name "SPI_CS") (class "Default")
      (node (ref "U3") (pin "13") (pinfunction "SPI_CS_13") (pintype "unspecified"))
    )
    (net (code "64") (name "SPI_MISO") (class "Default")
      (node (ref "U3") (pin "10") (pinfunction "SPI_MISO_10") (pintype "unspecified"))
    )
    (net (code "65") (name "SPI_MOSI") (class "Default")
      (node (ref "U3") (pin "11") (pinfunction "SPI_MOSI_11") (pintype "unspecified"))
    )
    (net (code "66") (name "TF_1V2") (class "Default")
      (node (ref "C13") (pin "1") (pinfunction "1_1") (pintype "input"))
      (node (ref "C18") (pin "1") (pinfunction "1_1") (pintype "input"))
      (node (ref "C20") (pin "1") (pinfunction "1_1") (pintype "input"))
      (node (ref "C23") (pin "2") (pinfunction "2_2") (pintype "input"))
      (node (ref "C26") (pin "2") (pinfunction "2_2") (pintype "input"))
      (node (ref "C29") (pin "2") (pinfunction "2_2") (pintype "input"))
      (node (ref "C39") (pin "1") (pinfunction "1_1") (pintype "input"))
      (node (ref "L1") (pin "2") (pinfunction "2_2") (pintype "unspecified"))
      (node (ref "TP2") (pin "1") (pinfunction "1_1") (pintype "input"))
      (node (ref "U6") (pin "13") (pinfunction "P2_VDD12_13") (pintype "unspecified"))
      (node (ref "U6") (pin "17") (pinfunction "VFB_17") (pintype "unspecified"))
      (node (ref "U6") (pin "27") (pinfunction "DVDD12_27") (pintype "unspecified"))
      (node (ref "U6") (pin "3") (pinfunction "P3_VDD12_3") (pintype "unspecified"))
      (node (ref "U6") (pin "40") (pinfunction "UP_VDD12_40") (pintype "unspecified"))
      (node (ref "U6") (pin "49") (pinfunction "P1_VDD12_49") (pintype "unspecified"))
      (node (ref "U6") (pin "58") (pinfunction "P4_VDD12_58") (pintype "unspecified"))
    )
    (net (code "67") (name "TF_CLK") (class "Default")
      (node (ref "CARD1") (pin "5") (pinfunction "CLX_5") (pintype "unspecified"))
      (node (ref "U2") (pin "7") (pinfunction "D1+_7") (pintype "unspecified"))
    )
    (net (code "68") (name "TF_CMD") (class "Default")
      (node (ref "CARD1") (pin "3") (pinfunction "CMD_3") (pintype "unspecified"))
      (node (ref "U2") (pin "8") (pinfunction "D1-_8") (pintype "unspecified"))
    )
    (net (code "69") (name "TF_DAT0") (class "Default")
      (node (ref "CARD1") (pin "7") (pinfunction "DAT0_7") (pintype "unspecified"))
      (node (ref "U2") (pin "6") (pinfunction "D0-_6") (pintype "unspecified"))
    )
    (net (code "70") (name "TF_DAT1") (class "Default")
      (node (ref "CARD1") (pin "8") (pinfunction "DAT1_8") (pintype "unspecified"))
      (node (ref "U2") (pin "5") (pinfunction "D0+_5") (pintype "unspecified"))
    )
    (net (code "71") (name "TF_DAT2") (class "Default")
      (node (ref "CARD1") (pin "1") (pinfunction "DAT2_1") (pintype "unspecified"))
      (node (ref "U2") (pin "11") (pinfunction "D2-_11") (pintype "unspecified"))
    )
    (net (code "72") (name "TF_DAT3") (class "Default")
      (node (ref "CARD1") (pin "2") (pinfunction "CD/DAT3_2") (pintype "unspecified"))
      (node (ref "U2") (pin "10") (pinfunction "D2+_10") (pintype "unspecified"))
    )
    (net (code "73") (name "TF_VCC") (class "Default")
      (node (ref "CARD1") (pin "4") (pinfunction "VDD_4") (pintype "unspecified"))
      (node (ref "Q4") (pin "3") (pinfunction "D_3") (pintype "unspecified"))
    )
    (net (code "74") (name "TF_VCC_EN") (class "Default")
      (node (ref "Q4") (pin "1") (pinfunction "G_1") (pintype "unspecified"))
    )
    (net (code "75") (name "TS_CLK") (class "Default")
      (node (ref "U1") (pin "5") (pinfunction "CLK_5") (pintype "unspecified"))
      (node (ref "U2") (pin "36") (pinfunction "D1+A_36") (pintype "unspecified"))
    )
    (net (code "76") (name "TS_CMD") (class "Default")
      (node (ref "U1") (pin "3") (pinfunction "CMD_3") (pintype "unspecified"))
      (node (ref "U2") (pin "35") (pinfunction "D1-A_35") (pintype "unspecified"))
    )
    (net (code "77") (name "TS_DAT0") (class "Default")
      (node (ref "U1") (pin "7") (pinfunction "DATA0_7") (pintype "unspecified"))
      (node (ref "U2") (pin "37") (pinfunction "D0-A_37") (pintype "unspecified"))
    )
    (net (code "78") (name "TS_DAT1") (class "Default")
      (node (ref "U1") (pin "8") (pinfunction "DATA1_8") (pintype "unspecified"))
      (node (ref "U2") (pin "38") (pinfunction "D0+A_38") (pintype "unspecified"))
    )
    (net (code "79") (name "TS_DAT2") (class "Default")
      (node (ref "U1") (pin "1") (pinfunction "DATA2_1") (pintype "unspecified"))
      (node (ref "U2") (pin "33") (pinfunction "D2-A_33") (pintype "unspecified"))
    )
    (net (code "80") (name "TS_DAT3") (class "Default")
      (node (ref "U1") (pin "2") (pinfunction "CD/DATA3_2") (pintype "unspecified"))
      (node (ref "U2") (pin "34") (pinfunction "D2+A_34") (pintype "unspecified"))
    )
    (net (code "81") (name "TS_RXD") (class "Default")
      (node (ref "H2") (pin "2") (pinfunction "2_2") (pintype "input"))
      (node (ref "U31") (pin "25") (pinfunction "RXD_25") (pintype "unspecified"))
    )
    (net (code "82") (name "TS_TXD") (class "Default")
      (node (ref "H2") (pin "1") (pinfunction "1_1") (pintype "input"))
      (node (ref "U31") (pin "26") (pinfunction "TXD_26") (pintype "unspecified"))
    )
    (net (code "83") (name "TS_VCC") (class "Default")
      (node (ref "Q3") (pin "2") (pinfunction "S_2") (pintype "unspecified"))
      (node (ref "U1") (pin "4") (pinfunction "VDD/3.3V_4") (pintype "unspecified"))
    )
    (net (code "84") (name "UP_CHO") (class "Default")
      (node (ref "U27") (pin "7") (pinfunction "PA1/ADC1_7") (pintype "unspecified"))
      (node (ref "U3") (pin "29") (pinfunction "SD_CDZ_29") (pintype "unspecified"))
    )
    (net (code "85") (name "UP_CLK") (class "Default")
      (node (ref "U2") (pin "27") (pinfunction "D1+B_27") (pintype "unspecified"))
      (node (ref "U3") (pin "20") (pinfunction "SD_CK_20") (pintype "unspecified"))
    )
    (net (code "86") (name "UP_CMD") (class "Default")
      (node (ref "U2") (pin "26") (pinfunction "D1-B_26") (pintype "unspecified"))
      (node (ref "U3") (pin "21") (pinfunction "SD_CM_21") (pintype "unspecified"))
    )
    (net (code "87") (name "UP_D+") (class "Default")
      (node (ref "U6") (pin "37") (pinfunction "UP_HS_DP_37") (pintype "unspecified"))
      (node (ref "U8") (pin "2") (pinfunction "I/O_2") (pintype "unspecified"))
      (node (ref "USB1") (pin "A6") (pinfunction "D+_A6") (pintype "unspecified"))
      (node (ref "USB1") (pin "B6") (pinfunction "D+_B6") (pintype "unspecified"))
    )
    (net (code "88") (name "UP_D-") (class "Default")
      (node (ref "U6") (pin "36") (pinfunction "UP_HS_DM_36") (pintype "unspecified"))
      (node (ref "U8") (pin "1") (pinfunction "I/O_1") (pintype "unspecified"))
      (node (ref "USB1") (pin "A7") (pinfunction "D-_A7") (pintype "unspecified"))
      (node (ref "USB1") (pin "B7") (pinfunction "D-_B7") (pintype "unspecified"))
    )
    (net (code "89") (name "UP_DAT0") (class "Default")
      (node (ref "U2") (pin "28") (pinfunction "D0-B_28") (pintype "unspecified"))
      (node (ref "U3") (pin "19") (pinfunction "SD_D0_19") (pintype "unspecified"))
    )
    (net (code "90") (name "UP_DAT1") (class "Default")
      (node (ref "U2") (pin "29") (pinfunction "D0+B_29") (pintype "unspecified"))
      (node (ref "U3") (pin "18") (pinfunction "SD_D1_18") (pintype "unspecified"))
    )
    (net (code "91") (name "UP_DAT2") (class "Default")
      (node (ref "U2") (pin "24") (pinfunction "D2-B_24") (pintype "unspecified"))
      (node (ref "U3") (pin "23") (pinfunction "SD_D2_23") (pintype "unspecified"))
    )
    (net (code "92") (name "UP_DAT3") (class "Default")
      (node (ref "U2") (pin "25") (pinfunction "D2+B_25") (pintype "unspecified"))
      (node (ref "U3") (pin "22") (pinfunction "SD_D3_22") (pintype "unspecified"))
    )
    (net (code "93") (name "UP_LED") (class "Default")
      (node (ref "LED9") (pin "2") (pinfunction "A_2") (pintype "input"))
      (node (ref "U3") (pin "14") (pinfunction "LED_14") (pintype "unspecified"))
    )
    (net (code "94") (name "UP_RX+") (class "Default")
      (node (ref "U11") (pin "18") (pinfunction "RX_P_18") (pintype "unspecified"))
      (node (ref "U6") (pin "41") (pinfunction "UP_SS_RXB_41") (pintype "unspecified"))
    )
    (net (code "95") (name "UP_RX-") (class "Default")
      (node (ref "U11") (pin "17") (pinfunction "RX_N_17") (pintype "unspecified"))
      (node (ref "U6") (pin "42") (pinfunction "UP_SS_RXA_42") (pintype "unspecified"))
    )
    (net (code "96") (name "UP_RX1+") (class "Default")
      (node (ref "U11") (pin "6") (pinfunction "RX1_P_6") (pintype "unspecified"))
      (node (ref "U7") (pin "5") (pinfunction "5_5") (pintype "unspecified"))
      (node (ref "U7") (pin "6") (pinfunction "6_6") (pintype "unspecified"))
      (node (ref "USB1") (pin "B11") (pinfunction "RX1+_B11") (pintype "unspecified"))
    )
    (net (code "97") (name "UP_RX1-") (class "Default")
      (node (ref "U11") (pin "7") (pinfunction "RX1_N_7") (pintype "unspecified"))
      (node (ref "U7") (pin "4") (pinfunction "4_4") (pintype "unspecified"))
      (node (ref "U7") (pin "7") (pinfunction "7_7") (pintype "unspecified"))
      (node (ref "USB1") (pin "B10") (pinfunction "RX1-_B10") (pintype "unspecified"))
    )
    (net (code "98") (name "UP_RX2+") (class "Default")
      (node (ref "U10") (pin "1") (pinfunction "1_1") (pintype "unspecified"))
      (node (ref "U10") (pin "10") (pinfunction "10_10") (pintype "unspecified"))
      (node (ref "U11") (pin "9") (pinfunction "RX2_P_9") (pintype "unspecified"))
      (node (ref "USB1") (pin "A11") (pinfunction "RX2+_A11") (pintype "unspecified"))
    )
    (net (code "99") (name "UP_RX2-") (class "Default")
      (node (ref "U10") (pin "2") (pinfunction "2_2") (pintype "unspecified"))
      (node (ref "U10") (pin "9") (pinfunction "9_9") (pintype "unspecified"))
      (node (ref "U11") (pin "8") (pinfunction "RX2_N_8") (pintype "unspecified"))
      (node (ref "USB1") (pin "A10") (pinfunction "RX2-_A10") (pintype "unspecified"))
    )
    (net (code "100") (name "UP_TX+") (class "Default")
      (node (ref "U11") (pin "21") (pinfunction "TXP_21") (pintype "unspecified"))
      (node (ref "U6") (pin "38") (pinfunction "UP_SS_TXB_38") (pintype "unspecified"))
    )
    (net (code "101") (name "UP_TX-") (class "Default")
      (node (ref "U11") (pin "20") (pinfunction "TXN_20") (pintype "unspecified"))
      (node (ref "U6") (pin "39") (pinfunction "UP_SS_TXA_39") (pintype "unspecified"))
    )
    (net (code "102") (name "UP_TX1+") (class "Default")
      (node (ref "C36") (pin "2") (pinfunction "2_2") (pintype "input"))
      (node (ref "U10") (pin "5") (pinfunction "5_5") (pintype "unspecified"))
      (node (ref "U10") (pin "6") (pinfunction "6_6") (pintype "unspecified"))
      (node (ref "USB1") (pin "A2") (pinfunction "TX1+_A2") (pintype "unspecified"))
    )
    (net (code "103") (name "UP_TX1-") (class "Default")
      (node (ref "C35") (pin "2") (pinfunction "2_2") (pintype "input"))
      (node (ref "U10") (pin "4") (pinfunction "4_4") (pintype "unspecified"))
      (node (ref "U10") (pin "7") (pinfunction "7_7") (pintype "unspecified"))
      (node (ref "USB1") (pin "A3") (pinfunction "TX1-_A3") (pintype "unspecified"))
    )
    (net (code "104") (name "UP_TX2+") (class "Default")
      (node (ref "C37") (pin "2") (pinfunction "2_2") (pintype "input"))
      (node (ref "U7") (pin "1") (pinfunction "1_1") (pintype "unspecified"))
      (node (ref "U7") (pin "10") (pinfunction "10_10") (pintype "unspecified"))
      (node (ref "USB1") (pin "B2") (pinfunction "TX2+_B2") (pintype "unspecified"))
    )
    (net (code "105") (name "UP_TX2-") (class "Default")
      (node (ref "C38") (pin "2") (pinfunction "2_2") (pintype "input"))
      (node (ref "U7") (pin "2") (pinfunction "2_2") (pintype "unspecified"))
      (node (ref "U7") (pin "9") (pinfunction "9_9") (pintype "unspecified"))
      (node (ref "USB1") (pin "B3") (pinfunction "TX2-_B3") (pintype "unspecified"))
    )
    (net (code "106") (name "UP_VCC") (class "Default")
      (node (ref "Q2") (pin "2") (pinfunction "S_2") (pintype "unspecified"))
      (node (ref "U3") (pin "26") (pinfunction "SD_VCC_26") (pintype "unspecified"))
    )
    (net (code "107") (name "UP_VCC_EN") (class "Default")
      (node (ref "Q3") (pin "1") (pinfunction "G_1") (pintype "unspecified"))
      (node (ref "U27") (pin "14") (pinfunction "PB0/ADC8_14") (pintype "unspecified"))
    )
    (net (code "108") (name "VCC") (class "Default")
      (node (ref "C1") (pin "2") (pinfunction "2_2") (pintype "input"))
      (node (ref "C10") (pin "2") (pinfunction "2_2") (pintype "input"))
      (node (ref "C19") (pin "2") (pinfunction "2_2") (pintype "input"))
      (node (ref "C21") (pin "2") (pinfunction "2_2") (pintype "input"))
      (node (ref "C24") (pin "1") (pinfunction "1_1") (pintype "input"))
      (node (ref "C30") (pin "2") (pinfunction "2_2") (pintype "input"))
      (node (ref "C31") (pin "2") (pinfunction "2_2") (pintype "input"))
      (node (ref "C34") (pin "1") (pinfunction "1_1") (pintype "input"))
      (node (ref "C4") (pin "2") (pinfunction "2_2") (pintype "input"))
      (node (ref "C6") (pin "1") (pinfunction "1_1") (pintype "input"))
      (node (ref "C8") (pin "1") (pinfunction "1_1") (pintype "input"))
      (node (ref "C89") (pin "2") (pinfunction "2_2") (pintype "unspecified"))
      (node (ref "C9") (pin "2") (pinfunction "2_2") (pintype "input"))
      (node (ref "C90") (pin "1") (pinfunction "1_1") (pintype "unspecified"))
      (node (ref "H3") (pin "1") (pinfunction "1_1") (pintype "unspecified"))
      (node (ref "L2") (pin "1") (pinfunction "1_1") (pintype "unspecified"))
      (node (ref "R13") (pin "1") (pinfunction "1_1") (pintype "input"))
      (node (ref "R18") (pin "1") (pinfunction "1_1") (pintype "input"))
      (node (ref "R29") (pin "1") (pinfunction "1_1") (pintype "input"))
      (node (ref "U2") (pin "1") (pinfunction "VCC_1") (pintype "unspecified"))
      (node (ref "U27") (pin "17") (pinfunction "VDD_17") (pintype "unspecified"))
      (node (ref "U27") (pin "5") (pinfunction "VDDA_5") (pintype "unspecified"))
      (node (ref "U3") (pin "15") (pinfunction "VBUS_15") (pintype "unspecified"))
      (node (ref "U3") (pin "16") (pinfunction "DVDD33_16") (pintype "unspecified"))
      (node (ref "U3") (pin "25") (pinfunction "DVDD33_25") (pintype "unspecified"))
      (node (ref "U3") (pin "30") (pinfunction "AVDD33_30") (pintype "unspecified"))
      (node (ref "U3") (pin "8") (pinfunction "AVDD33_8") (pintype "unspecified"))
      (node (ref "U31") (pin "6") (pinfunction "V3_6") (pintype "unspecified"))
      (node (ref "U31") (pin "7") (pinfunction "VDD5_7") (pintype "unspecified"))
      (node (ref "U6") (pin "20") (pinfunction "VDD5_20") (pintype "unspecified"))
      (node (ref "U6") (pin "21") (pinfunction "VDD33/VIO33_21") (pintype "unspecified"))
      (node (ref "U6") (pin "25") (pinfunction "VBUS_DET/PWR_CC_25") (pintype "unspecified"))
      (node (ref "U6") (pin "35") (pinfunction "AVDD33_35") (pintype "unspecified"))
      (node (ref "U6") (pin "54") (pinfunction "VIO33_54") (pintype "unspecified"))
      (node (ref "X6") (pin "4") (pinfunction "VDD_4") (pintype "unspecified"))
    )
    (net (code "109") (name "unconnected-(CARD1-PadCD)") (class "Default")
      (node (ref "CARD1") (pin "CD") (pinfunction "CD_CD") (pintype "unspecified+no_connect"))
    )
    (net (code "110") (name "unconnected-(U2-CEC-Pad15)") (class "Default")
      (node (ref "U2") (pin "15") (pinfunction "CEC_15") (pintype "unspecified+no_connect"))
    )
    (net (code "111") (name "unconnected-(U2-CEC_A-Pad18)") (class "Default")
      (node (ref "U2") (pin "18") (pinfunction "CEC_A_18") (pintype "unspecified+no_connect"))
    )
    (net (code "112") (name "unconnected-(U2-CEC_B-Pad20)") (class "Default")
      (node (ref "U2") (pin "20") (pinfunction "CEC_B_20") (pintype "unspecified+no_connect"))
    )
    (net (code "113") (name "unconnected-(U2-D3+-Pad12)") (class "Default")
      (node (ref "U2") (pin "12") (pinfunction "D3+_12") (pintype "unspecified+no_connect"))
    )
    (net (code "114") (name "unconnected-(U2-D3+A-Pad32)") (class "Default")
      (node (ref "U2") (pin "32") (pinfunction "D3+A_32") (pintype "unspecified+no_connect"))
    )
    (net (code "115") (name "unconnected-(U2-D3+B-Pad23)") (class "Default")
      (node (ref "U2") (pin "23") (pinfunction "D3+B_23") (pintype "unspecified+no_connect"))
    )
    (net (code "116") (name "unconnected-(U2-D3--Pad13)") (class "Default")
      (node (ref "U2") (pin "13") (pinfunction "D3-_13") (pintype "unspecified+no_connect"))
    )
    (net (code "117") (name "unconnected-(U2-D3-A-Pad31)") (class "Default")
      (node (ref "U2") (pin "31") (pinfunction "D3-A_31") (pintype "unspecified+no_connect"))
    )
    (net (code "118") (name "unconnected-(U2-D3-B-Pad22)") (class "Default")
      (node (ref "U2") (pin "22") (pinfunction "D3-B_22") (pintype "unspecified+no_connect"))
    )
    (net (code "119") (name "unconnected-(U2-HPD-Pad14)") (class "Default")
      (node (ref "U2") (pin "14") (pinfunction "HPD_14") (pintype "unspecified+no_connect"))
    )
    (net (code "120") (name "unconnected-(U2-HPD_A-Pad19)") (class "Default")
      (node (ref "U2") (pin "19") (pinfunction "HPD_A_19") (pintype "unspecified+no_connect"))
    )
    (net (code "121") (name "unconnected-(U2-HPD_B-Pad21)") (class "Default")
      (node (ref "U2") (pin "21") (pinfunction "HPD_B_21") (pintype "unspecified+no_connect"))
    )
    (net (code "122") (name "unconnected-(U2-NC-Pad9)") (class "Default")
      (node (ref "U2") (pin "9") (pinfunction "NC_9") (pintype "unspecified+no_connect"))
    )
    (net (code "123") (name "unconnected-(U2-NC-Pad30)") (class "Default")
      (node (ref "U2") (pin "30") (pinfunction "NC_30") (pintype "unspecified+no_connect"))
    )
    (net (code "124") (name "unconnected-(U2-SCL-Pad3)") (class "Default")
      (node (ref "U2") (pin "3") (pinfunction "SCL_3") (pintype "unspecified+no_connect"))
    )
    (net (code "125") (name "unconnected-(U2-SCL_A-Pad42)") (class "Default")
      (node (ref "U2") (pin "42") (pinfunction "SCL_A_42") (pintype "unspecified+no_connect"))
    )
    (net (code "126") (name "unconnected-(U2-SCL_B-Pad40)") (class "Default")
      (node (ref "U2") (pin "40") (pinfunction "SCL_B_40") (pintype "unspecified+no_connect"))
    )
    (net (code "127") (name "unconnected-(U2-SDA-Pad4)") (class "Default")
      (node (ref "U2") (pin "4") (pinfunction "SDA_4") (pintype "unspecified+no_connect"))
    )
    (net (code "128") (name "unconnected-(U2-SDA_A-Pad41)") (class "Default")
      (node (ref "U2") (pin "41") (pinfunction "SDA_A_41") (pintype "unspecified+no_connect"))
    )
    (net (code "129") (name "unconnected-(U2-SDA_B-Pad39)") (class "Default")
      (node (ref "U2") (pin "39") (pinfunction "SDA_B_39") (pintype "unspecified+no_connect"))
    )
    (net (code "130") (name "unconnected-(U3-X2-Pad7)") (class "Default")
      (node (ref "U3") (pin "7") (pinfunction "X2_7") (pintype "unspecified+no_connect"))
    )
    (net (code "131") (name "unconnected-(U6-CFG0-Pad22)") (class "Default")
      (node (ref "U6") (pin "22") (pinfunction "CFG0_22") (pintype "unspecified+no_connect"))
    )
    (net (code "132") (name "unconnected-(U6-CFG1-Pad23)") (class "Default")
      (node (ref "U6") (pin "23") (pinfunction "CFG1_23") (pintype "unspecified+no_connect"))
    )
    (net (code "133") (name "unconnected-(U6-NC-Pad8)") (class "Default")
      (node (ref "U6") (pin "8") (pinfunction "NC_8") (pintype "unspecified+no_connect"))
    )
    (net (code "134") (name "unconnected-(U6-NC-Pad43)") (class "Default")
      (node (ref "U6") (pin "43") (pinfunction "NC_43") (pintype "unspecified+no_connect"))
    )
    (net (code "135") (name "unconnected-(U6-NC-Pad46)") (class "Default")
      (node (ref "U6") (pin "46") (pinfunction "NC_46") (pintype "unspecified+no_connect"))
    )
    (net (code "136") (name "unconnected-(U6-NC-Pad55)") (class "Default")
      (node (ref "U6") (pin "55") (pinfunction "NC_55") (pintype "unspecified+no_connect"))
    )
    (net (code "137") (name "unconnected-(U6-NC-Pad61)") (class "Default")
      (node (ref "U6") (pin "61") (pinfunction "NC_61") (pintype "unspecified+no_connect"))
    )
    (net (code "138") (name "unconnected-(U6-NC-Pad62)") (class "Default")
      (node (ref "U6") (pin "62") (pinfunction "NC_62") (pintype "unspecified+no_connect"))
    )
    (net (code "139") (name "unconnected-(U6-P1_SS_RXA-Pad51)") (class "Default")
      (node (ref "U6") (pin "51") (pinfunction "P1_SS_RXA_51") (pintype "unspecified+no_connect"))
    )
    (net (code "140") (name "unconnected-(U6-P1_SS_RXB-Pad50)") (class "Default")
      (node (ref "U6") (pin "50") (pinfunction "P1_SS_RXB_50") (pintype "unspecified+no_connect"))
    )
    (net (code "141") (name "unconnected-(U6-P1_SS_TXA-Pad48)") (class "Default")
      (node (ref "U6") (pin "48") (pinfunction "P1_SS_TXA_48") (pintype "unspecified+no_connect"))
    )
    (net (code "142") (name "unconnected-(U6-P1_SS_TXB-Pad47)") (class "Default")
      (node (ref "U6") (pin "47") (pinfunction "P1_SS_TXB_47") (pintype "unspecified+no_connect"))
    )
    (net (code "143") (name "unconnected-(U6-P2_SS_RXA-Pad15)") (class "Default")
      (node (ref "U6") (pin "15") (pinfunction "P2_SS_RXA_15") (pintype "unspecified+no_connect"))
    )
    (net (code "144") (name "unconnected-(U6-P2_SS_RXB-Pad14)") (class "Default")
      (node (ref "U6") (pin "14") (pinfunction "P2_SS_RXB_14") (pintype "unspecified+no_connect"))
    )
    (net (code "145") (name "unconnected-(U6-P2_SS_TXA-Pad12)") (class "Default")
      (node (ref "U6") (pin "12") (pinfunction "P2_SS_TXA_12") (pintype "unspecified+no_connect"))
    )
    (net (code "146") (name "unconnected-(U6-P2_SS_TXB-Pad11)") (class "Default")
      (node (ref "U6") (pin "11") (pinfunction "P2_SS_TXB_11") (pintype "unspecified+no_connect"))
    )
    (net (code "147") (name "unconnected-(U6-P4_SS_RXA-Pad60)") (class "Default")
      (node (ref "U6") (pin "60") (pinfunction "P4_SS_RXA_60") (pintype "unspecified+no_connect"))
    )
    (net (code "148") (name "unconnected-(U6-P4_SS_RXB-Pad59)") (class "Default")
      (node (ref "U6") (pin "59") (pinfunction "P4_SS_RXB_59") (pintype "unspecified+no_connect"))
    )
    (net (code "149") (name "unconnected-(U6-P4_SS_TXA-Pad57)") (class "Default")
      (node (ref "U6") (pin "57") (pinfunction "P4_SS_TXA_57") (pintype "unspecified+no_connect"))
    )
    (net (code "150") (name "unconnected-(U6-P4_SS_TXB-Pad56)") (class "Default")
      (node (ref "U6") (pin "56") (pinfunction "P4_SS_TXB_56") (pintype "unspecified+no_connect"))
    )
    (net (code "151") (name "unconnected-(U6-PWREN#-Pad34)") (class "Default")
      (node (ref "U6") (pin "34") (pinfunction "PWREN#_34") (pintype "unspecified+no_connect"))
    )
    (net (code "152") (name "unconnected-(U6-RESET#-Pad24)") (class "Default")
      (node (ref "U6") (pin "24") (pinfunction "RESET#_24") (pintype "unspecified+no_connect"))
    )
    (net (code "153") (name "unconnected-(U6-RSVD{slash}HUB_CC-Pad26)") (class "Default")
      (node (ref "U6") (pin "26") (pinfunction "RSVD/HUB_CC_26") (pintype "unspecified+no_connect"))
    )
    (net (code "154") (name "unconnected-(U6-SPI_MISO{slash}SDA-Pad30)") (class "Default")
      (node (ref "U6") (pin "30") (pinfunction "SPI_MISO/SDA_30") (pintype "unspecified+no_connect"))
    )
    (net (code "155") (name "unconnected-(U6-SPI_MOSI-Pad28)") (class "Default")
      (node (ref "U6") (pin "28") (pinfunction "SPI_MOSI_28") (pintype "unspecified+no_connect"))
    )
    (net (code "156") (name "unconnected-(U6-SPI_SCK{slash}SCL-Pad29)") (class "Default")
      (node (ref "U6") (pin "29") (pinfunction "SPI_SCK/SCL_29") (pintype "unspecified+no_connect"))
    )
    (net (code "157") (name "unconnected-(U6-SPI_SCS{slash}PDHUB#-Pad31)") (class "Default")
      (node (ref "U6") (pin "31") (pinfunction "SPI_SCS/PDHUB#_31") (pintype "unspecified+no_connect"))
    )
    (net (code "158") (name "unconnected-(U11-Attached_Status-Pad16)") (class "Default")
      (node (ref "U11") (pin "16") (pinfunction "Attached_Status_16") (pintype "unspecified"))
    )
    (net (code "159") (name "unconnected-(U11-CurrentSettingout-Pad14)") (class "Default")
      (node (ref "U11") (pin "14") (pinfunction "CurrentSettingout_14") (pintype "unspecified+no_connect"))
    )
    (net (code "160") (name "unconnected-(U11-CurrentSettingout-Pad15)") (class "Default")
      (node (ref "U11") (pin "15") (pinfunction "CurrentSettingout_15") (pintype "unspecified+no_connect"))
    )
    (net (code "161") (name "unconnected-(U11-ORI_STATUS-Pad22)") (class "Default")
      (node (ref "U11") (pin "22") (pinfunction "ORI_STATUS_22") (pintype "unspecified+no_connect"))
    )
    (net (code "162") (name "unconnected-(U11-Vconn_OC-Pad11)") (class "Default")
      (node (ref "U11") (pin "11") (pinfunction "Vconn_OC_11") (pintype "unspecified+no_connect"))
    )
    (net (code "163") (name "unconnected-(U11-Vconn_UVLO-Pad12)") (class "Default")
      (node (ref "U11") (pin "12") (pinfunction "Vconn_UVLO_12") (pintype "unspecified+no_connect"))
    )
    (net (code "164") (name "unconnected-(U27-NRST-Pad4)") (class "Default")
      (node (ref "U27") (pin "4") (pinfunction "NRST_4") (pintype "unspecified+no_connect"))
    )
    (net (code "165") (name "unconnected-(U27-PA0{slash}WKUP{slash}ADC0-Pad6)") (class "Default")
      (node (ref "U27") (pin "6") (pinfunction "PA0/WKUP/ADC0_6") (pintype "unspecified+no_connect"))
    )
    (net (code "166") (name "unconnected-(U27-PA9-Pad18)") (class "Default")
      (node (ref "U27") (pin "18") (pinfunction "PA9_18") (pintype "unspecified+no_connect"))
    )
    (net (code "167") (name "unconnected-(U27-PA13{slash}SWDIO-Pad21)") (class "Default")
      (node (ref "U27") (pin "21") (pinfunction "PA13/SWDIO_21") (pintype "unspecified+no_connect"))
    )
    (net (code "168") (name "unconnected-(U27-PA14{slash}SWCLK-Pad22)") (class "Default")
      (node (ref "U27") (pin "22") (pinfunction "PA14/SWCLK_22") (pintype "unspecified+no_connect"))
    )
    (net (code "169") (name "unconnected-(U27-PA15-Pad23)") (class "Default")
      (node (ref "U27") (pin "23") (pinfunction "PA15_23") (pintype "unspecified+no_connect"))
    )
    (net (code "170") (name "unconnected-(U27-PB1{slash}ADC9-Pad15)") (class "Default")
      (node (ref "U27") (pin "15") (pinfunction "PB1/ADC9_15") (pintype "unspecified+no_connect"))
    )
    (net (code "171") (name "unconnected-(U27-PB4-Pad25)") (class "Default")
      (node (ref "U27") (pin "25") (pinfunction "PB4_25") (pintype "unspecified+no_connect"))
    )
    (net (code "172") (name "unconnected-(U27-PB5-Pad26)") (class "Default")
      (node (ref "U27") (pin "26") (pinfunction "PB5_26") (pintype "unspecified+no_connect"))
    )
    (net (code "173") (name "unconnected-(U28-FLAG#-Pad3)") (class "Default")
      (node (ref "U28") (pin "3") (pinfunction "FLAG#_3") (pintype "unspecified+no_connect"))
    )
    (net (code "174") (name "unconnected-(U29-FLAG#-Pad3)") (class "Default")
      (node (ref "U29") (pin "3") (pinfunction "FLAG#_3") (pintype "unspecified+no_connect"))
    )
    (net (code "175") (name "unconnected-(U31-ACT#-Pad10)") (class "Default")
      (node (ref "U31") (pin "10") (pinfunction "ACT#_10") (pintype "unspecified+no_connect"))
    )
    (net (code "176") (name "unconnected-(U31-CTS-Pad23)") (class "Default")
      (node (ref "U31") (pin "23") (pinfunction "CTS_23") (pintype "unspecified+no_connect"))
    )
    (net (code "177") (name "unconnected-(U31-DCD-Pad1)") (class "Default")
      (node (ref "U31") (pin "1") (pinfunction "DCD_1") (pintype "unspecified+no_connect"))
    )
    (net (code "178") (name "unconnected-(U31-DSR-Pad27)") (class "Default")
      (node (ref "U31") (pin "27") (pinfunction "DSR_27") (pintype "unspecified+no_connect"))
    )
    (net (code "179") (name "unconnected-(U31-DTR-Pad28)") (class "Default")
      (node (ref "U31") (pin "28") (pinfunction "DTR_28") (pintype "unspecified+no_connect"))
    )
    (net (code "180") (name "unconnected-(U31-GPIO5-Pad21)") (class "Default")
      (node (ref "U31") (pin "21") (pinfunction "GPIO5_21") (pintype "unspecified+no_connect"))
    )
    (net (code "181") (name "unconnected-(U31-GPIO6-Pad20)") (class "Default")
      (node (ref "U31") (pin "20") (pinfunction "GPIO6_20") (pintype "unspecified+no_connect"))
    )
    (net (code "182") (name "unconnected-(U31-NC-Pad13)") (class "Default")
      (node (ref "U31") (pin "13") (pinfunction "NC_13") (pintype "unspecified+no_connect"))
    )
    (net (code "183") (name "unconnected-(U31-NC-Pad14)") (class "Default")
      (node (ref "U31") (pin "14") (pinfunction "NC_14") (pintype "unspecified+no_connect"))
    )
    (net (code "184") (name "unconnected-(U31-NC-Pad15)") (class "Default")
      (node (ref "U31") (pin "15") (pinfunction "NC_15") (pintype "unspecified+no_connect"))
    )
    (net (code "185") (name "unconnected-(U31-RI-Pad2)") (class "Default")
      (node (ref "U31") (pin "2") (pinfunction "RI_2") (pintype "unspecified+no_connect"))
    )
    (net (code "186") (name "unconnected-(U31-RST#-Pad9)") (class "Default")
      (node (ref "U31") (pin "9") (pinfunction "RST#_9") (pintype "unspecified+no_connect"))
    )
    (net (code "187") (name "unconnected-(U31-RTS-Pad24)") (class "Default")
      (node (ref "U31") (pin "24") (pinfunction "RTS_24") (pintype "unspecified+no_connect"))
    )
    (net (code "188") (name "unconnected-(U31-RXS{slash}GPIO1-Pad18)") (class "Default")
      (node (ref "U31") (pin "18") (pinfunction "RXS/GPIO1_18") (pintype "unspecified+no_connect"))
    )
    (net (code "189") (name "unconnected-(U31-SUSPEND#-Pad11)") (class "Default")
      (node (ref "U31") (pin "11") (pinfunction "SUSPEND#_11") (pintype "unspecified+no_connect"))
    )
    (net (code "190") (name "unconnected-(U31-SUSPEND-Pad12)") (class "Default")
      (node (ref "U31") (pin "12") (pinfunction "SUSPEND_12") (pintype "unspecified+no_connect"))
    )
    (net (code "191") (name "unconnected-(U31-TNOW{slash}GPIO2-Pad17)") (class "Default")
      (node (ref "U31") (pin "17") (pinfunction "TNOW/GPIO2_17") (pintype "unspecified+no_connect"))
    )
    (net (code "192") (name "unconnected-(U31-TXS{slash}GPIO0-Pad19)") (class "Default")
      (node (ref "U31") (pin "19") (pinfunction "TXS/GPIO0_19") (pintype "unspecified+no_connect"))
    )
    (net (code "193") (name "unconnected-(U31-V3-Pad22)") (class "Default")
      (node (ref "U31") (pin "22") (pinfunction "V3_22") (pintype "unspecified"))
    )
    (net (code "194") (name "unconnected-(U31-WAKEUP{slash}GPIO3-Pad16)") (class "Default")
      (node (ref "U31") (pin "16") (pinfunction "WAKEUP/GPIO3_16") (pintype "unspecified+no_connect"))
    )
    (net (code "195") (name "unconnected-(USB1-SBU1-PadA8)") (class "Default")
      (node (ref "USB1") (pin "A8") (pinfunction "SBU1_A8") (pintype "unspecified+no_connect"))
    )
    (net (code "196") (name "unconnected-(USB1-SBU2-PadB8)") (class "Default")
      (node (ref "USB1") (pin "B8") (pinfunction "SBU2_B8") (pintype "unspecified+no_connect"))
    )
    (net (code "197") (name "unconnected-(X6-Tri-state-Pad1)") (class "Default")
      (node (ref "X6") (pin "1") (pinfunction "Tri-state_1") (pintype "unspecified+no_connect"))
    )
    (net (code "198") (name "unconnected-(X7-GND-Pad2)") (class "Default")
      (node (ref "X7") (pin "2") (pinfunction "GND_2") (pintype "input+no_connect"))
    )
    (net (code "199") (name "unconnected-(X7-GND-Pad4)") (class "Default")
      (node (ref "X7") (pin "4") (pinfunction "GND_4") (pintype "input+no_connect"))
    )
    (net (code "200") (name "unconnected-(X8-GND-Pad2)") (class "Default")
      (node (ref "X8") (pin "2") (pinfunction "GND_2") (pintype "input+no_connect"))
    )
    (net (code "201") (name "unconnected-(X8-GND-Pad4)") (class "Default")
      (node (ref "X8") (pin "4") (pinfunction "GND_4") (pintype "input+no_connect"))
    )
  )
)
